# DaughterBoard_Slots.net
KiCad netlist of a schematic drawn in Altium Designer
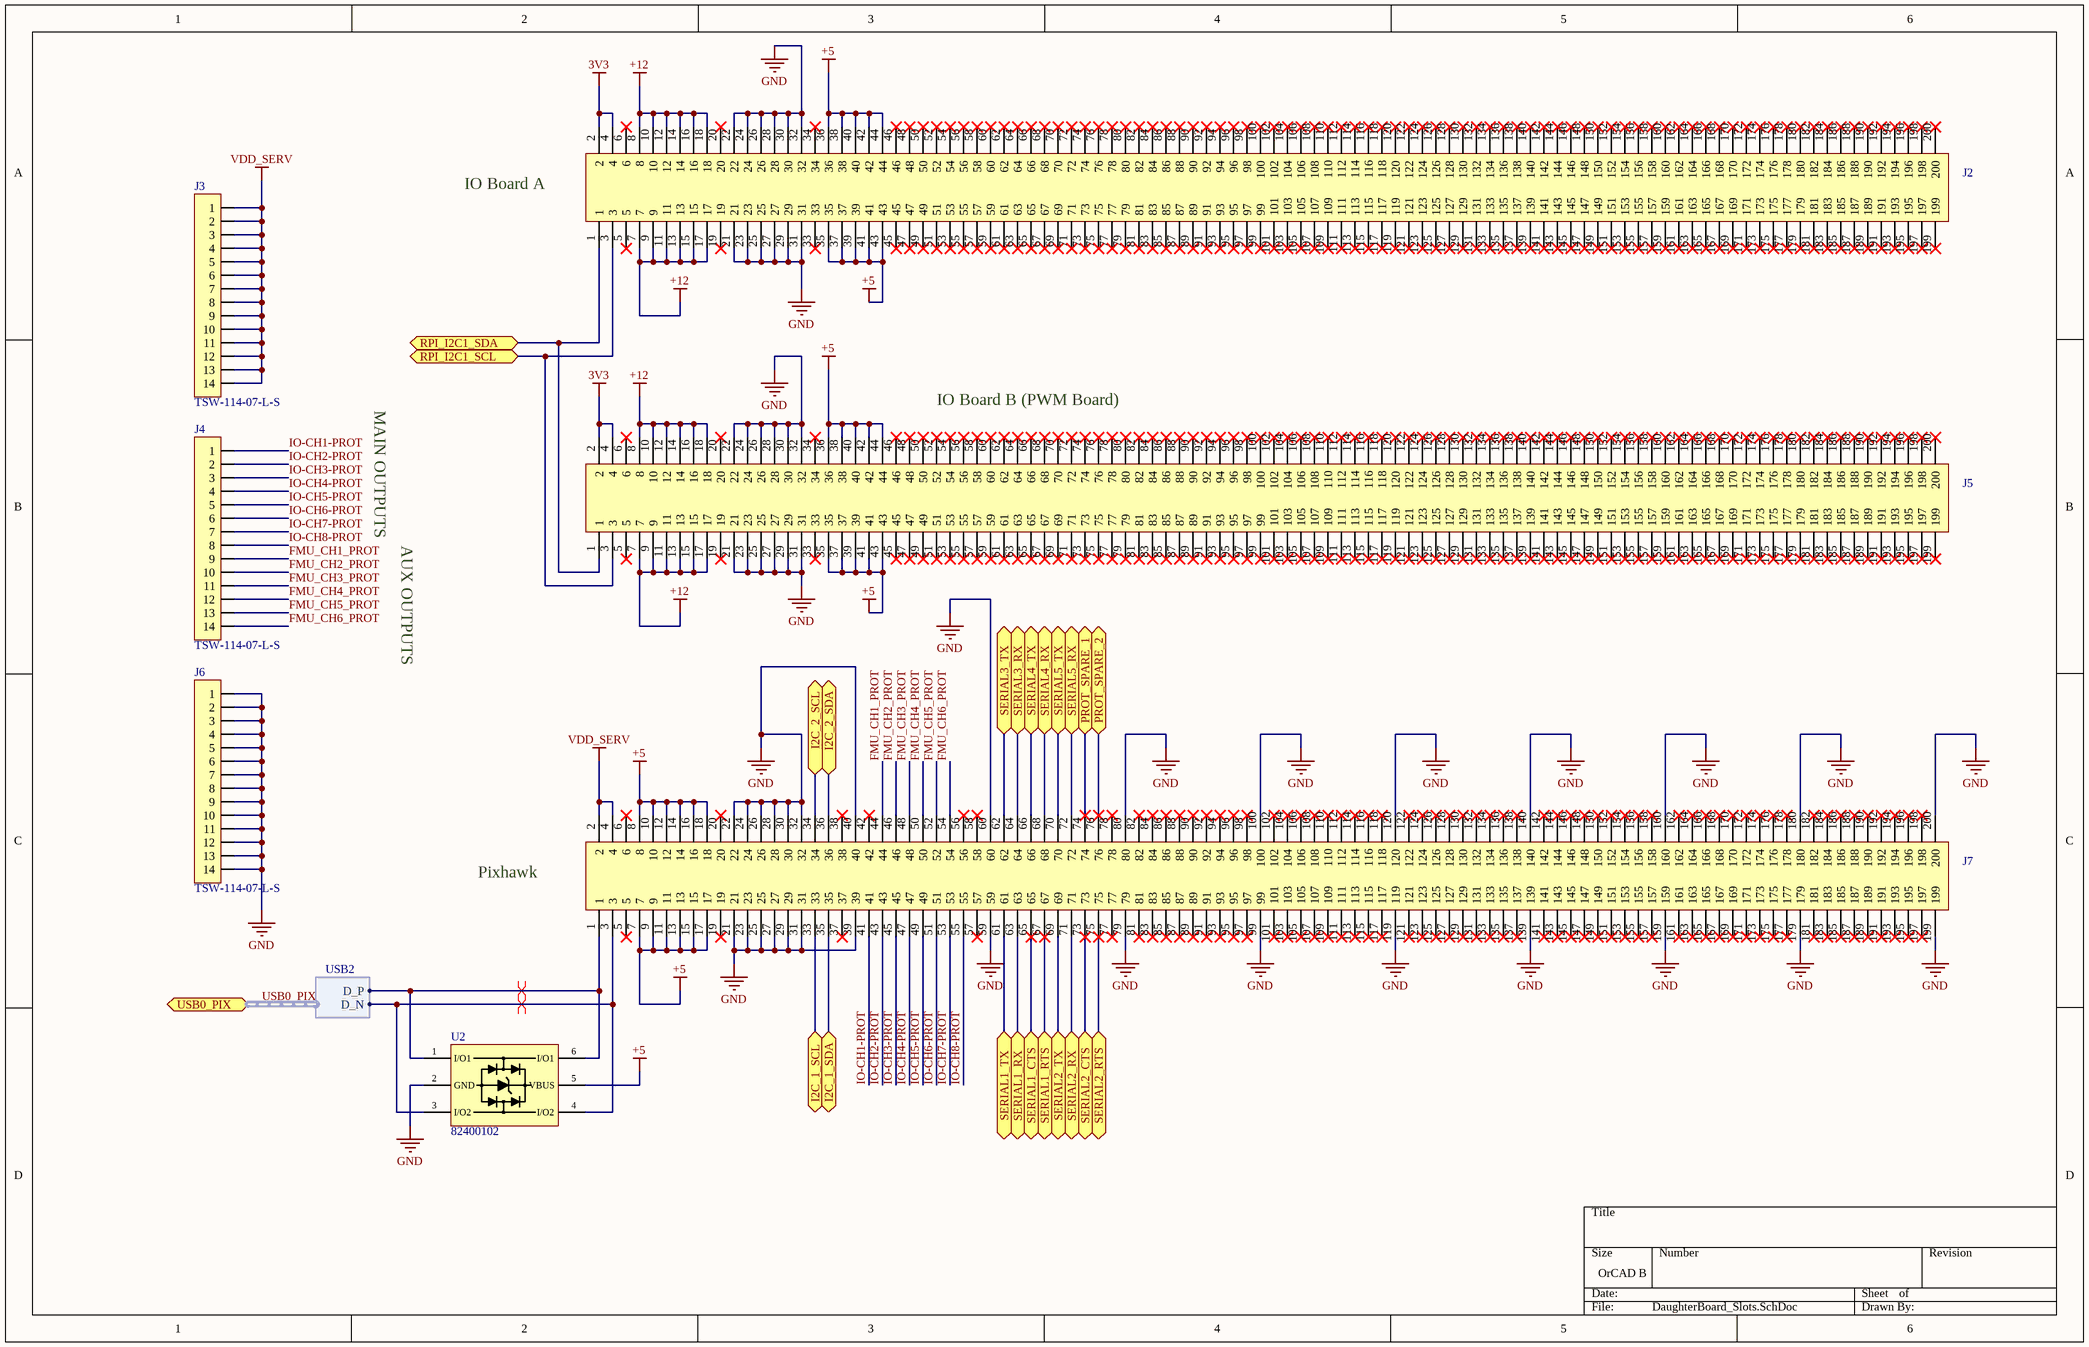
[diagram p0: DaughterBoard_Slots.SchDoc]

(export (version "E")
  (design (tool "Eeschema 10.0.6"))
  (components
    (comp (ref "J2")
      (value "conn-100x2_0")
      (footprint "DDR1-SODIMM-V")
      (description "Card-Edge Socket, DDR1 SODIMM (2.5V), 200-pin, Vertical")
      (fields (field (name "PART NUMBER") "CONN-00056") (field (name "MANUFACTURER") "TE Connectivity"))
      (libsource (lib "Connectors$") (part "CONN-00056"))
    )
    (comp (ref "J3")
      (value "TSW-114-07-L-S")
      (footprint "HDDR_14x1_0")
      (description "Header, 14x1, 0.1\"")
      (fields (field (name "PART NUMBER") "CONN-00117") (field (name "MANUFACTURER") "Samtec"))
      (libsource (lib "Connectors$") (part "CONN-00117"))
    )
    (comp (ref "J4")
      (value "TSW-114-07-L-S")
      (footprint "HDDR_14x1_0")
      (description "Header, 14x1, 0.1\"")
      (fields (field (name "PART NUMBER") "CONN-00117") (field (name "MANUFACTURER") "Samtec"))
      (libsource (lib "Connectors$") (part "CONN-00117"))
    )
    (comp (ref "J5")
      (value "conn-100x2_0")
      (footprint "DDR1-SODIMM-V")
      (description "Card-Edge Socket, DDR1 SODIMM (2.5V), 200-pin, Vertical")
      (fields (field (name "PART NUMBER") "CONN-00056") (field (name "MANUFACTURER") "TE Connectivity"))
      (libsource (lib "Connectors$") (part "CONN-00056"))
    )
    (comp (ref "J6")
      (value "TSW-114-07-L-S")
      (footprint "HDDR_14x1_0")
      (description "Header, 14x1, 0.1\"")
      (fields (field (name "PART NUMBER") "CONN-00117") (field (name "MANUFACTURER") "Samtec"))
      (libsource (lib "Connectors$") (part "CONN-00117"))
    )
    (comp (ref "J7")
      (value "conn-100x2_0")
      (footprint "DDR1-SODIMM-V")
      (description "Card-Edge Socket, DDR1 SODIMM (2.5V), 200-pin, Vertical")
      (fields (field (name "PART NUMBER") "CONN-00056") (field (name "MANUFACTURER") "TE Connectivity"))
      (libsource (lib "Connectors$") (part "CONN-00056"))
    )
    (comp (ref "U2")
      (value "82400102")
      (footprint "sot-23-6")
      (description "ESD Protec, 2-Ch, 2.5pF, 17V clamping voltage, SOT23-6")
      (fields (field (name "PART NUMBER") "DIO-00069") (field (name "MANUFACTURER") "ST"))
      (libsource (lib "Diodes$") (part "DIO-00069"))
    )
  )
  (nets
    (net (code "2") (name "+5") (class "Default")
      (node (ref "J2") (pin "35") (pinfunction "35_35") (pintype "passive"))
      (node (ref "J2") (pin "36") (pinfunction "36_36") (pintype "passive"))
      (node (ref "J2") (pin "37") (pinfunction "37_37") (pintype "passive"))
      (node (ref "J2") (pin "38") (pinfunction "38_38") (pintype "passive"))
      (node (ref "J2") (pin "39") (pinfunction "39_39") (pintype "passive"))
      (node (ref "J2") (pin "40") (pinfunction "40_40") (pintype "passive"))
      (node (ref "J2") (pin "41") (pinfunction "41_41") (pintype "passive"))
      (node (ref "J2") (pin "42") (pinfunction "42_42") (pintype "passive"))
      (node (ref "J2") (pin "43") (pinfunction "43_43") (pintype "passive"))
      (node (ref "J2") (pin "44") (pinfunction "44_44") (pintype "passive"))
      (node (ref "J5") (pin "35") (pinfunction "35_35") (pintype "passive"))
      (node (ref "J5") (pin "36") (pinfunction "36_36") (pintype "passive"))
      (node (ref "J5") (pin "37") (pinfunction "37_37") (pintype "passive"))
      (node (ref "J5") (pin "38") (pinfunction "38_38") (pintype "passive"))
      (node (ref "J5") (pin "39") (pinfunction "39_39") (pintype "passive"))
      (node (ref "J5") (pin "40") (pinfunction "40_40") (pintype "passive"))
      (node (ref "J5") (pin "41") (pinfunction "41_41") (pintype "passive"))
      (node (ref "J5") (pin "42") (pinfunction "42_42") (pintype "passive"))
      (node (ref "J5") (pin "43") (pinfunction "43_43") (pintype "passive"))
      (node (ref "J5") (pin "44") (pinfunction "44_44") (pintype "passive"))
      (node (ref "J7") (pin "10") (pinfunction "10_10") (pintype "passive"))
      (node (ref "J7") (pin "11") (pinfunction "11_11") (pintype "passive"))
      (node (ref "J7") (pin "12") (pinfunction "12_12") (pintype "passive"))
      (node (ref "J7") (pin "13") (pinfunction "13_13") (pintype "passive"))
      (node (ref "J7") (pin "14") (pinfunction "14_14") (pintype "passive"))
      (node (ref "J7") (pin "15") (pinfunction "15_15") (pintype "passive"))
      (node (ref "J7") (pin "16") (pinfunction "16_16") (pintype "passive"))
      (node (ref "J7") (pin "17") (pinfunction "17_17") (pintype "passive"))
      (node (ref "J7") (pin "18") (pinfunction "18_18") (pintype "passive"))
      (node (ref "J7") (pin "7") (pinfunction "7_7") (pintype "passive"))
      (node (ref "J7") (pin "8") (pinfunction "8_8") (pintype "passive"))
      (node (ref "J7") (pin "9") (pinfunction "9_9") (pintype "passive"))
      (node (ref "U2") (pin "5") (pinfunction "VBUS_5") (pintype "passive"))
    )
    (net (code "3") (name "+12") (class "Default")
      (node (ref "J2") (pin "10") (pinfunction "10_10") (pintype "passive"))
      (node (ref "J2") (pin "11") (pinfunction "11_11") (pintype "passive"))
      (node (ref "J2") (pin "12") (pinfunction "12_12") (pintype "passive"))
      (node (ref "J2") (pin "13") (pinfunction "13_13") (pintype "passive"))
      (node (ref "J2") (pin "14") (pinfunction "14_14") (pintype "passive"))
      (node (ref "J2") (pin "15") (pinfunction "15_15") (pintype "passive"))
      (node (ref "J2") (pin "16") (pinfunction "16_16") (pintype "passive"))
      (node (ref "J2") (pin "17") (pinfunction "17_17") (pintype "passive"))
      (node (ref "J2") (pin "18") (pinfunction "18_18") (pintype "passive"))
      (node (ref "J2") (pin "7") (pinfunction "7_7") (pintype "passive"))
      (node (ref "J2") (pin "8") (pinfunction "8_8") (pintype "passive"))
      (node (ref "J2") (pin "9") (pinfunction "9_9") (pintype "passive"))
      (node (ref "J5") (pin "10") (pinfunction "10_10") (pintype "passive"))
      (node (ref "J5") (pin "11") (pinfunction "11_11") (pintype "passive"))
      (node (ref "J5") (pin "12") (pinfunction "12_12") (pintype "passive"))
      (node (ref "J5") (pin "13") (pinfunction "13_13") (pintype "passive"))
      (node (ref "J5") (pin "14") (pinfunction "14_14") (pintype "passive"))
      (node (ref "J5") (pin "15") (pinfunction "15_15") (pintype "passive"))
      (node (ref "J5") (pin "16") (pinfunction "16_16") (pintype "passive"))
      (node (ref "J5") (pin "17") (pinfunction "17_17") (pintype "passive"))
      (node (ref "J5") (pin "18") (pinfunction "18_18") (pintype "passive"))
      (node (ref "J5") (pin "7") (pinfunction "7_7") (pintype "passive"))
      (node (ref "J5") (pin "8") (pinfunction "8_8") (pintype "passive"))
      (node (ref "J5") (pin "9") (pinfunction "9_9") (pintype "passive"))
    )
    (net (code "4") (name "/FMU_CH1_PROT") (class "Default")
      (node (ref "J4") (pin "9") (pinfunction "9_9") (pintype "passive"))
      (node (ref "J7") (pin "44") (pinfunction "44_44") (pintype "passive"))
    )
    (net (code "5") (name "/FMU_CH2_PROT") (class "Default")
      (node (ref "J4") (pin "10") (pinfunction "10_10") (pintype "passive"))
      (node (ref "J7") (pin "46") (pinfunction "46_46") (pintype "passive"))
    )
    (net (code "6") (name "/FMU_CH3_PROT") (class "Default")
      (node (ref "J4") (pin "11") (pinfunction "11_11") (pintype "passive"))
      (node (ref "J7") (pin "48") (pinfunction "48_48") (pintype "passive"))
    )
    (net (code "7") (name "/FMU_CH4_PROT") (class "Default")
      (node (ref "J4") (pin "12") (pinfunction "12_12") (pintype "passive"))
      (node (ref "J7") (pin "50") (pinfunction "50_50") (pintype "passive"))
    )
    (net (code "8") (name "/FMU_CH5_PROT") (class "Default")
      (node (ref "J4") (pin "13") (pinfunction "13_13") (pintype "passive"))
      (node (ref "J7") (pin "52") (pinfunction "52_52") (pintype "passive"))
    )
    (net (code "9") (name "/FMU_CH6_PROT") (class "Default")
      (node (ref "J4") (pin "14") (pinfunction "14_14") (pintype "passive"))
      (node (ref "J7") (pin "54") (pinfunction "54_54") (pintype "passive"))
    )
    (net (code "10") (name "/I2C_1_SCL") (class "Default")
      (node (ref "J7") (pin "33") (pinfunction "33_33") (pintype "passive"))
    )
    (net (code "11") (name "/I2C_1_SDA") (class "Default")
      (node (ref "J7") (pin "35") (pinfunction "35_35") (pintype "passive"))
    )
    (net (code "12") (name "/I2C_2_SCL") (class "Default")
      (node (ref "J7") (pin "34") (pinfunction "34_34") (pintype "passive"))
    )
    (net (code "13") (name "/I2C_2_SDA") (class "Default")
      (node (ref "J7") (pin "36") (pinfunction "36_36") (pintype "passive"))
    )
    (net (code "14") (name "/IO-CH1-PROT") (class "Default")
      (node (ref "J4") (pin "1") (pinfunction "1_1") (pintype "passive"))
      (node (ref "J7") (pin "41") (pinfunction "41_41") (pintype "passive"))
    )
    (net (code "15") (name "/IO-CH2-PROT") (class "Default")
      (node (ref "J4") (pin "2") (pinfunction "2_2") (pintype "passive"))
      (node (ref "J7") (pin "43") (pinfunction "43_43") (pintype "passive"))
    )
    (net (code "16") (name "/IO-CH3-PROT") (class "Default")
      (node (ref "J4") (pin "3") (pinfunction "3_3") (pintype "passive"))
      (node (ref "J7") (pin "45") (pinfunction "45_45") (pintype "passive"))
    )
    (net (code "17") (name "/IO-CH4-PROT") (class "Default")
      (node (ref "J4") (pin "4") (pinfunction "4_4") (pintype "passive"))
      (node (ref "J7") (pin "47") (pinfunction "47_47") (pintype "passive"))
    )
    (net (code "18") (name "/IO-CH5-PROT") (class "Default")
      (node (ref "J4") (pin "5") (pinfunction "5_5") (pintype "passive"))
      (node (ref "J7") (pin "49") (pinfunction "49_49") (pintype "passive"))
    )
    (net (code "19") (name "/IO-CH6-PROT") (class "Default")
      (node (ref "J4") (pin "6") (pinfunction "6_6") (pintype "passive"))
      (node (ref "J7") (pin "51") (pinfunction "51_51") (pintype "passive"))
    )
    (net (code "20") (name "/IO-CH7-PROT") (class "Default")
      (node (ref "J4") (pin "7") (pinfunction "7_7") (pintype "passive"))
      (node (ref "J7") (pin "53") (pinfunction "53_53") (pintype "passive"))
    )
    (net (code "21") (name "/IO-CH8-PROT") (class "Default")
      (node (ref "J4") (pin "8") (pinfunction "8_8") (pintype "passive"))
      (node (ref "J7") (pin "55") (pinfunction "55_55") (pintype "passive"))
    )
    (net (code "22") (name "/PROT_SPARE_1") (class "Default")
      (node (ref "J7") (pin "74") (pinfunction "74_74") (pintype "passive+no_connect"))
    )
    (net (code "23") (name "/PROT_SPARE_2") (class "Default")
      (node (ref "J7") (pin "76") (pinfunction "76_76") (pintype "passive+no_connect"))
    )
    (net (code "24") (name "/RPI_I2C1_SCL") (class "Default")
      (node (ref "J2") (pin "3") (pinfunction "3_3") (pintype "passive"))
      (node (ref "J5") (pin "3") (pinfunction "3_3") (pintype "passive"))
    )
    (net (code "25") (name "/RPI_I2C1_SDA") (class "Default")
      (node (ref "J2") (pin "1") (pinfunction "1_1") (pintype "passive"))
      (node (ref "J5") (pin "1") (pinfunction "1_1") (pintype "passive"))
    )
    (net (code "26") (name "/SERIAL1_CTS") (class "Default")
      (node (ref "J7") (pin "65") (pinfunction "65_65") (pintype "passive+no_connect"))
    )
    (net (code "27") (name "/SERIAL1_RTS") (class "Default")
      (node (ref "J7") (pin "67") (pinfunction "67_67") (pintype "passive+no_connect"))
    )
    (net (code "28") (name "/SERIAL1_RX") (class "Default")
      (node (ref "J7") (pin "63") (pinfunction "63_63") (pintype "passive"))
    )
    (net (code "29") (name "/SERIAL1_TX") (class "Default")
      (node (ref "J7") (pin "61") (pinfunction "61_61") (pintype "passive"))
    )
    (net (code "30") (name "/SERIAL2_CTS") (class "Default")
      (node (ref "J7") (pin "73") (pinfunction "73_73") (pintype "passive+no_connect"))
    )
    (net (code "31") (name "/SERIAL2_RTS") (class "Default")
      (node (ref "J7") (pin "75") (pinfunction "75_75") (pintype "passive+no_connect"))
    )
    (net (code "32") (name "/SERIAL2_RX") (class "Default")
      (node (ref "J7") (pin "71") (pinfunction "71_71") (pintype "passive"))
    )
    (net (code "33") (name "/SERIAL2_TX") (class "Default")
      (node (ref "J7") (pin "69") (pinfunction "69_69") (pintype "passive"))
    )
    (net (code "34") (name "/SERIAL3_RX") (class "Default")
      (node (ref "J7") (pin "64") (pinfunction "64_64") (pintype "passive"))
    )
    (net (code "35") (name "/SERIAL3_TX") (class "Default")
      (node (ref "J7") (pin "62") (pinfunction "62_62") (pintype "passive"))
    )
    (net (code "36") (name "/SERIAL4_RX") (class "Default")
      (node (ref "J7") (pin "68") (pinfunction "68_68") (pintype "passive"))
    )
    (net (code "37") (name "/SERIAL4_TX") (class "Default")
      (node (ref "J7") (pin "66") (pinfunction "66_66") (pintype "passive"))
    )
    (net (code "38") (name "/SERIAL5_RX") (class "Default")
      (node (ref "J7") (pin "72") (pinfunction "72_72") (pintype "passive"))
    )
    (net (code "39") (name "/SERIAL5_TX") (class "Default")
      (node (ref "J7") (pin "70") (pinfunction "70_70") (pintype "passive"))
    )
    (net (code "41") (name "3V3") (class "Default")
      (node (ref "J2") (pin "2") (pinfunction "2_2") (pintype "passive"))
      (node (ref "J2") (pin "4") (pinfunction "4_4") (pintype "passive"))
      (node (ref "J5") (pin "2") (pinfunction "2_2") (pintype "passive"))
      (node (ref "J5") (pin "4") (pinfunction "4_4") (pintype "passive"))
    )
    (net (code "42") (name "GND") (class "Default")
      (node (ref "J2") (pin "21") (pinfunction "21_21") (pintype "passive"))
      (node (ref "J2") (pin "22") (pinfunction "22_22") (pintype "passive"))
      (node (ref "J2") (pin "23") (pinfunction "23_23") (pintype "passive"))
      (node (ref "J2") (pin "24") (pinfunction "24_24") (pintype "passive"))
      (node (ref "J2") (pin "25") (pinfunction "25_25") (pintype "passive"))
      (node (ref "J2") (pin "26") (pinfunction "26_26") (pintype "passive"))
      (node (ref "J2") (pin "27") (pinfunction "27_27") (pintype "passive"))
      (node (ref "J2") (pin "28") (pinfunction "28_28") (pintype "passive"))
      (node (ref "J2") (pin "29") (pinfunction "29_29") (pintype "passive"))
      (node (ref "J2") (pin "30") (pinfunction "30_30") (pintype "passive"))
      (node (ref "J2") (pin "31") (pinfunction "31_31") (pintype "passive"))
      (node (ref "J2") (pin "32") (pinfunction "32_32") (pintype "passive"))
      (node (ref "J5") (pin "21") (pinfunction "21_21") (pintype "passive"))
      (node (ref "J5") (pin "22") (pinfunction "22_22") (pintype "passive"))
      (node (ref "J5") (pin "23") (pinfunction "23_23") (pintype "passive"))
      (node (ref "J5") (pin "24") (pinfunction "24_24") (pintype "passive"))
      (node (ref "J5") (pin "25") (pinfunction "25_25") (pintype "passive"))
      (node (ref "J5") (pin "26") (pinfunction "26_26") (pintype "passive"))
      (node (ref "J5") (pin "27") (pinfunction "27_27") (pintype "passive"))
      (node (ref "J5") (pin "28") (pinfunction "28_28") (pintype "passive"))
      (node (ref "J5") (pin "29") (pinfunction "29_29") (pintype "passive"))
      (node (ref "J5") (pin "30") (pinfunction "30_30") (pintype "passive"))
      (node (ref "J5") (pin "31") (pinfunction "31_31") (pintype "passive"))
      (node (ref "J5") (pin "32") (pinfunction "32_32") (pintype "passive"))
      (node (ref "J6") (pin "1") (pinfunction "1_1") (pintype "passive"))
      (node (ref "J6") (pin "10") (pinfunction "10_10") (pintype "passive"))
      (node (ref "J6") (pin "11") (pinfunction "11_11") (pintype "passive"))
      (node (ref "J6") (pin "12") (pinfunction "12_12") (pintype "passive"))
      (node (ref "J6") (pin "13") (pinfunction "13_13") (pintype "passive"))
      (node (ref "J6") (pin "14") (pinfunction "14_14") (pintype "passive"))
      (node (ref "J6") (pin "2") (pinfunction "2_2") (pintype "passive"))
      (node (ref "J6") (pin "3") (pinfunction "3_3") (pintype "passive"))
      (node (ref "J6") (pin "4") (pinfunction "4_4") (pintype "passive"))
      (node (ref "J6") (pin "5") (pinfunction "5_5") (pintype "passive"))
      (node (ref "J6") (pin "6") (pinfunction "6_6") (pintype "passive"))
      (node (ref "J6") (pin "7") (pinfunction "7_7") (pintype "passive"))
      (node (ref "J6") (pin "8") (pinfunction "8_8") (pintype "passive"))
      (node (ref "J6") (pin "9") (pinfunction "9_9") (pintype "passive"))
      (node (ref "J7") (pin "100") (pinfunction "100_100") (pintype "passive"))
      (node (ref "J7") (pin "119") (pinfunction "119_119") (pintype "passive"))
      (node (ref "J7") (pin "120") (pinfunction "120_120") (pintype "passive"))
      (node (ref "J7") (pin "139") (pinfunction "139_139") (pintype "passive"))
      (node (ref "J7") (pin "140") (pinfunction "140_140") (pintype "passive"))
      (node (ref "J7") (pin "159") (pinfunction "159_159") (pintype "passive"))
      (node (ref "J7") (pin "160") (pinfunction "160_160") (pintype "passive"))
      (node (ref "J7") (pin "179") (pinfunction "179_179") (pintype "passive"))
      (node (ref "J7") (pin "180") (pinfunction "180_180") (pintype "passive"))
      (node (ref "J7") (pin "199") (pinfunction "199_199") (pintype "passive"))
      (node (ref "J7") (pin "200") (pinfunction "200_200") (pintype "passive"))
      (node (ref "J7") (pin "21") (pinfunction "21_21") (pintype "passive"))
      (node (ref "J7") (pin "22") (pinfunction "22_22") (pintype "passive"))
      (node (ref "J7") (pin "23") (pinfunction "23_23") (pintype "passive"))
      (node (ref "J7") (pin "24") (pinfunction "24_24") (pintype "passive"))
      (node (ref "J7") (pin "25") (pinfunction "25_25") (pintype "passive"))
      (node (ref "J7") (pin "26") (pinfunction "26_26") (pintype "passive"))
      (node (ref "J7") (pin "27") (pinfunction "27_27") (pintype "passive"))
      (node (ref "J7") (pin "28") (pinfunction "28_28") (pintype "passive"))
      (node (ref "J7") (pin "29") (pinfunction "29_29") (pintype "passive"))
      (node (ref "J7") (pin "30") (pinfunction "30_30") (pintype "passive"))
      (node (ref "J7") (pin "31") (pinfunction "31_31") (pintype "passive"))
      (node (ref "J7") (pin "32") (pinfunction "32_32") (pintype "passive"))
      (node (ref "J7") (pin "39") (pinfunction "39_39") (pintype "passive"))
      (node (ref "J7") (pin "40") (pinfunction "40_40") (pintype "passive"))
      (node (ref "J7") (pin "59") (pinfunction "59_59") (pintype "passive"))
      (node (ref "J7") (pin "60") (pinfunction "60_60") (pintype "passive"))
      (node (ref "J7") (pin "79") (pinfunction "79_79") (pintype "passive"))
      (node (ref "J7") (pin "80") (pinfunction "80_80") (pintype "passive"))
      (node (ref "J7") (pin "99") (pinfunction "99_99") (pintype "passive"))
      (node (ref "U2") (pin "2") (pinfunction "GND_2") (pintype "passive"))
    )
    (net (code "43") (name "Net-(J7-Pad1)") (class "Default")
      (node (ref "J7") (pin "1") (pinfunction "1_1") (pintype "passive"))
      (node (ref "U2") (pin "1") (pinfunction "I/O1_1") (pintype "passive"))
      (node (ref "U2") (pin "6") (pinfunction "I/O1_6") (pintype "passive"))
    )
    (net (code "44") (name "Net-(J7-Pad3)") (class "Default")
      (node (ref "J7") (pin "3") (pinfunction "3_3") (pintype "passive"))
      (node (ref "U2") (pin "3") (pinfunction "I/O2_3") (pintype "passive"))
      (node (ref "U2") (pin "4") (pinfunction "I/O2_4") (pintype "passive"))
    )
    (net (code "45") (name "VDD_SERV") (class "Default")
      (node (ref "J3") (pin "1") (pinfunction "1_1") (pintype "passive"))
      (node (ref "J3") (pin "10") (pinfunction "10_10") (pintype "passive"))
      (node (ref "J3") (pin "11") (pinfunction "11_11") (pintype "passive"))
      (node (ref "J3") (pin "12") (pinfunction "12_12") (pintype "passive"))
      (node (ref "J3") (pin "13") (pinfunction "13_13") (pintype "passive"))
      (node (ref "J3") (pin "14") (pinfunction "14_14") (pintype "passive"))
      (node (ref "J3") (pin "2") (pinfunction "2_2") (pintype "passive"))
      (node (ref "J3") (pin "3") (pinfunction "3_3") (pintype "passive"))
      (node (ref "J3") (pin "4") (pinfunction "4_4") (pintype "passive"))
      (node (ref "J3") (pin "5") (pinfunction "5_5") (pintype "passive"))
      (node (ref "J3") (pin "6") (pinfunction "6_6") (pintype "passive"))
      (node (ref "J3") (pin "7") (pinfunction "7_7") (pintype "passive"))
      (node (ref "J3") (pin "8") (pinfunction "8_8") (pintype "passive"))
      (node (ref "J3") (pin "9") (pinfunction "9_9") (pintype "passive"))
      (node (ref "J7") (pin "2") (pinfunction "2_2") (pintype "passive"))
      (node (ref "J7") (pin "4") (pinfunction "4_4") (pintype "passive"))
    )
    (net (code "46") (name "unconnected-(J2-Pad5)") (class "Default")
      (node (ref "J2") (pin "5") (pinfunction "5_5") (pintype "passive+no_connect"))
    )
    (net (code "47") (name "unconnected-(J2-Pad6)") (class "Default")
      (node (ref "J2") (pin "6") (pinfunction "6_6") (pintype "passive+no_connect"))
    )
    (net (code "48") (name "unconnected-(J2-Pad19)") (class "Default")
      (node (ref "J2") (pin "19") (pinfunction "19_19") (pintype "passive+no_connect"))
    )
    (net (code "49") (name "unconnected-(J2-Pad20)") (class "Default")
      (node (ref "J2") (pin "20") (pinfunction "20_20") (pintype "passive+no_connect"))
    )
    (net (code "50") (name "unconnected-(J2-Pad33)") (class "Default")
      (node (ref "J2") (pin "33") (pinfunction "33_33") (pintype "passive+no_connect"))
    )
    (net (code "51") (name "unconnected-(J2-Pad34)") (class "Default")
      (node (ref "J2") (pin "34") (pinfunction "34_34") (pintype "passive+no_connect"))
    )
    (net (code "52") (name "unconnected-(J2-Pad45)") (class "Default")
      (node (ref "J2") (pin "45") (pinfunction "45_45") (pintype "passive+no_connect"))
    )
    (net (code "53") (name "unconnected-(J2-Pad46)") (class "Default")
      (node (ref "J2") (pin "46") (pinfunction "46_46") (pintype "passive+no_connect"))
    )
    (net (code "54") (name "unconnected-(J2-Pad47)") (class "Default")
      (node (ref "J2") (pin "47") (pinfunction "47_47") (pintype "passive+no_connect"))
    )
    (net (code "55") (name "unconnected-(J2-Pad48)") (class "Default")
      (node (ref "J2") (pin "48") (pinfunction "48_48") (pintype "passive+no_connect"))
    )
    (net (code "56") (name "unconnected-(J2-Pad49)") (class "Default")
      (node (ref "J2") (pin "49") (pinfunction "49_49") (pintype "passive+no_connect"))
    )
    (net (code "57") (name "unconnected-(J2-Pad50)") (class "Default")
      (node (ref "J2") (pin "50") (pinfunction "50_50") (pintype "passive+no_connect"))
    )
    (net (code "58") (name "unconnected-(J2-Pad51)") (class "Default")
      (node (ref "J2") (pin "51") (pinfunction "51_51") (pintype "passive+no_connect"))
    )
    (net (code "59") (name "unconnected-(J2-Pad52)") (class "Default")
      (node (ref "J2") (pin "52") (pinfunction "52_52") (pintype "passive+no_connect"))
    )
    (net (code "60") (name "unconnected-(J2-Pad53)") (class "Default")
      (node (ref "J2") (pin "53") (pinfunction "53_53") (pintype "passive+no_connect"))
    )
    (net (code "61") (name "unconnected-(J2-Pad54)") (class "Default")
      (node (ref "J2") (pin "54") (pinfunction "54_54") (pintype "passive+no_connect"))
    )
    (net (code "62") (name "unconnected-(J2-Pad55)") (class "Default")
      (node (ref "J2") (pin "55") (pinfunction "55_55") (pintype "passive+no_connect"))
    )
    (net (code "63") (name "unconnected-(J2-Pad56)") (class "Default")
      (node (ref "J2") (pin "56") (pinfunction "56_56") (pintype "passive+no_connect"))
    )
    (net (code "64") (name "unconnected-(J2-Pad57)") (class "Default")
      (node (ref "J2") (pin "57") (pinfunction "57_57") (pintype "passive+no_connect"))
    )
    (net (code "65") (name "unconnected-(J2-Pad58)") (class "Default")
      (node (ref "J2") (pin "58") (pinfunction "58_58") (pintype "passive+no_connect"))
    )
    (net (code "66") (name "unconnected-(J2-Pad59)") (class "Default")
      (node (ref "J2") (pin "59") (pinfunction "59_59") (pintype "passive+no_connect"))
    )
    (net (code "67") (name "unconnected-(J2-Pad60)") (class "Default")
      (node (ref "J2") (pin "60") (pinfunction "60_60") (pintype "passive+no_connect"))
    )
    (net (code "68") (name "unconnected-(J2-Pad61)") (class "Default")
      (node (ref "J2") (pin "61") (pinfunction "61_61") (pintype "passive+no_connect"))
    )
    (net (code "69") (name "unconnected-(J2-Pad62)") (class "Default")
      (node (ref "J2") (pin "62") (pinfunction "62_62") (pintype "passive+no_connect"))
    )
    (net (code "70") (name "unconnected-(J2-Pad63)") (class "Default")
      (node (ref "J2") (pin "63") (pinfunction "63_63") (pintype "passive+no_connect"))
    )
    (net (code "71") (name "unconnected-(J2-Pad64)") (class "Default")
      (node (ref "J2") (pin "64") (pinfunction "64_64") (pintype "passive+no_connect"))
    )
    (net (code "72") (name "unconnected-(J2-Pad65)") (class "Default")
      (node (ref "J2") (pin "65") (pinfunction "65_65") (pintype "passive+no_connect"))
    )
    (net (code "73") (name "unconnected-(J2-Pad66)") (class "Default")
      (node (ref "J2") (pin "66") (pinfunction "66_66") (pintype "passive+no_connect"))
    )
    (net (code "74") (name "unconnected-(J2-Pad67)") (class "Default")
      (node (ref "J2") (pin "67") (pinfunction "67_67") (pintype "passive+no_connect"))
    )
    (net (code "75") (name "unconnected-(J2-Pad68)") (class "Default")
      (node (ref "J2") (pin "68") (pinfunction "68_68") (pintype "passive+no_connect"))
    )
    (net (code "76") (name "unconnected-(J2-Pad69)") (class "Default")
      (node (ref "J2") (pin "69") (pinfunction "69_69") (pintype "passive+no_connect"))
    )
    (net (code "77") (name "unconnected-(J2-Pad70)") (class "Default")
      (node (ref "J2") (pin "70") (pinfunction "70_70") (pintype "passive+no_connect"))
    )
    (net (code "78") (name "unconnected-(J2-Pad71)") (class "Default")
      (node (ref "J2") (pin "71") (pinfunction "71_71") (pintype "passive+no_connect"))
    )
    (net (code "79") (name "unconnected-(J2-Pad72)") (class "Default")
      (node (ref "J2") (pin "72") (pinfunction "72_72") (pintype "passive+no_connect"))
    )
    (net (code "80") (name "unconnected-(J2-Pad73)") (class "Default")
      (node (ref "J2") (pin "73") (pinfunction "73_73") (pintype "passive+no_connect"))
    )
    (net (code "81") (name "unconnected-(J2-Pad74)") (class "Default")
      (node (ref "J2") (pin "74") (pinfunction "74_74") (pintype "passive+no_connect"))
    )
    (net (code "82") (name "unconnected-(J2-Pad75)") (class "Default")
      (node (ref "J2") (pin "75") (pinfunction "75_75") (pintype "passive+no_connect"))
    )
    (net (code "83") (name "unconnected-(J2-Pad76)") (class "Default")
      (node (ref "J2") (pin "76") (pinfunction "76_76") (pintype "passive+no_connect"))
    )
    (net (code "84") (name "unconnected-(J2-Pad77)") (class "Default")
      (node (ref "J2") (pin "77") (pinfunction "77_77") (pintype "passive+no_connect"))
    )
    (net (code "85") (name "unconnected-(J2-Pad78)") (class "Default")
      (node (ref "J2") (pin "78") (pinfunction "78_78") (pintype "passive+no_connect"))
    )
    (net (code "86") (name "unconnected-(J2-Pad79)") (class "Default")
      (node (ref "J2") (pin "79") (pinfunction "79_79") (pintype "passive+no_connect"))
    )
    (net (code "87") (name "unconnected-(J2-Pad80)") (class "Default")
      (node (ref "J2") (pin "80") (pinfunction "80_80") (pintype "passive+no_connect"))
    )
    (net (code "88") (name "unconnected-(J2-Pad81)") (class "Default")
      (node (ref "J2") (pin "81") (pinfunction "81_81") (pintype "passive+no_connect"))
    )
    (net (code "89") (name "unconnected-(J2-Pad82)") (class "Default")
      (node (ref "J2") (pin "82") (pinfunction "82_82") (pintype "passive+no_connect"))
    )
    (net (code "90") (name "unconnected-(J2-Pad83)") (class "Default")
      (node (ref "J2") (pin "83") (pinfunction "83_83") (pintype "passive+no_connect"))
    )
    (net (code "91") (name "unconnected-(J2-Pad84)") (class "Default")
      (node (ref "J2") (pin "84") (pinfunction "84_84") (pintype "passive+no_connect"))
    )
    (net (code "92") (name "unconnected-(J2-Pad85)") (class "Default")
      (node (ref "J2") (pin "85") (pinfunction "85_85") (pintype "passive+no_connect"))
    )
    (net (code "93") (name "unconnected-(J2-Pad86)") (class "Default")
      (node (ref "J2") (pin "86") (pinfunction "86_86") (pintype "passive+no_connect"))
    )
    (net (code "94") (name "unconnected-(J2-Pad87)") (class "Default")
      (node (ref "J2") (pin "87") (pinfunction "87_87") (pintype "passive+no_connect"))
    )
    (net (code "95") (name "unconnected-(J2-Pad88)") (class "Default")
      (node (ref "J2") (pin "88") (pinfunction "88_88") (pintype "passive+no_connect"))
    )
    (net (code "96") (name "unconnected-(J2-Pad89)") (class "Default")
      (node (ref "J2") (pin "89") (pinfunction "89_89") (pintype "passive+no_connect"))
    )
    (net (code "97") (name "unconnected-(J2-Pad90)") (class "Default")
      (node (ref "J2") (pin "90") (pinfunction "90_90") (pintype "passive+no_connect"))
    )
    (net (code "98") (name "unconnected-(J2-Pad91)") (class "Default")
      (node (ref "J2") (pin "91") (pinfunction "91_91") (pintype "passive+no_connect"))
    )
    (net (code "99") (name "unconnected-(J2-Pad92)") (class "Default")
      (node (ref "J2") (pin "92") (pinfunction "92_92") (pintype "passive+no_connect"))
    )
    (net (code "100") (name "unconnected-(J2-Pad93)") (class "Default")
      (node (ref "J2") (pin "93") (pinfunction "93_93") (pintype "passive+no_connect"))
    )
    (net (code "101") (name "unconnected-(J2-Pad94)") (class "Default")
      (node (ref "J2") (pin "94") (pinfunction "94_94") (pintype "passive+no_connect"))
    )
    (net (code "102") (name "unconnected-(J2-Pad95)") (class "Default")
      (node (ref "J2") (pin "95") (pinfunction "95_95") (pintype "passive+no_connect"))
    )
    (net (code "103") (name "unconnected-(J2-Pad96)") (class "Default")
      (node (ref "J2") (pin "96") (pinfunction "96_96") (pintype "passive+no_connect"))
    )
    (net (code "104") (name "unconnected-(J2-Pad97)") (class "Default")
      (node (ref "J2") (pin "97") (pinfunction "97_97") (pintype "passive+no_connect"))
    )
    (net (code "105") (name "unconnected-(J2-Pad98)") (class "Default")
      (node (ref "J2") (pin "98") (pinfunction "98_98") (pintype "passive+no_connect"))
    )
    (net (code "106") (name "unconnected-(J2-Pad99)") (class "Default")
      (node (ref "J2") (pin "99") (pinfunction "99_99") (pintype "passive+no_connect"))
    )
    (net (code "107") (name "unconnected-(J2-Pad100)") (class "Default")
      (node (ref "J2") (pin "100") (pinfunction "100_100") (pintype "passive+no_connect"))
    )
    (net (code "108") (name "unconnected-(J2-Pad101)") (class "Default")
      (node (ref "J2") (pin "101") (pinfunction "101_101") (pintype "passive+no_connect"))
    )
    (net (code "109") (name "unconnected-(J2-Pad102)") (class "Default")
      (node (ref "J2") (pin "102") (pinfunction "102_102") (pintype "passive+no_connect"))
    )
    (net (code "110") (name "unconnected-(J2-Pad103)") (class "Default")
      (node (ref "J2") (pin "103") (pinfunction "103_103") (pintype "passive+no_connect"))
    )
    (net (code "111") (name "unconnected-(J2-Pad104)") (class "Default")
      (node (ref "J2") (pin "104") (pinfunction "104_104") (pintype "passive+no_connect"))
    )
    (net (code "112") (name "unconnected-(J2-Pad105)") (class "Default")
      (node (ref "J2") (pin "105") (pinfunction "105_105") (pintype "passive+no_connect"))
    )
    (net (code "113") (name "unconnected-(J2-Pad106)") (class "Default")
      (node (ref "J2") (pin "106") (pinfunction "106_106") (pintype "passive+no_connect"))
    )
    (net (code "114") (name "unconnected-(J2-Pad107)") (class "Default")
      (node (ref "J2") (pin "107") (pinfunction "107_107") (pintype "passive+no_connect"))
    )
    (net (code "115") (name "unconnected-(J2-Pad108)") (class "Default")
      (node (ref "J2") (pin "108") (pinfunction "108_108") (pintype "passive+no_connect"))
    )
    (net (code "116") (name "unconnected-(J2-Pad109)") (class "Default")
      (node (ref "J2") (pin "109") (pinfunction "109_109") (pintype "passive+no_connect"))
    )
    (net (code "117") (name "unconnected-(J2-Pad110)") (class "Default")
      (node (ref "J2") (pin "110") (pinfunction "110_110") (pintype "passive+no_connect"))
    )
    (net (code "118") (name "unconnected-(J2-Pad111)") (class "Default")
      (node (ref "J2") (pin "111") (pinfunction "111_111") (pintype "passive+no_connect"))
    )
    (net (code "119") (name "unconnected-(J2-Pad112)") (class "Default")
      (node (ref "J2") (pin "112") (pinfunction "112_112") (pintype "passive+no_connect"))
    )
    (net (code "120") (name "unconnected-(J2-Pad113)") (class "Default")
      (node (ref "J2") (pin "113") (pinfunction "113_113") (pintype "passive+no_connect"))
    )
    (net (code "121") (name "unconnected-(J2-Pad114)") (class "Default")
      (node (ref "J2") (pin "114") (pinfunction "114_114") (pintype "passive+no_connect"))
    )
    (net (code "122") (name "unconnected-(J2-Pad115)") (class "Default")
      (node (ref "J2") (pin "115") (pinfunction "115_115") (pintype "passive+no_connect"))
    )
    (net (code "123") (name "unconnected-(J2-Pad116)") (class "Default")
      (node (ref "J2") (pin "116") (pinfunction "116_116") (pintype "passive+no_connect"))
    )
    (net (code "124") (name "unconnected-(J2-Pad117)") (class "Default")
      (node (ref "J2") (pin "117") (pinfunction "117_117") (pintype "passive+no_connect"))
    )
    (net (code "125") (name "unconnected-(J2-Pad118)") (class "Default")
      (node (ref "J2") (pin "118") (pinfunction "118_118") (pintype "passive+no_connect"))
    )
    (net (code "126") (name "unconnected-(J2-Pad119)") (class "Default")
      (node (ref "J2") (pin "119") (pinfunction "119_119") (pintype "passive+no_connect"))
    )
    (net (code "127") (name "unconnected-(J2-Pad120)") (class "Default")
      (node (ref "J2") (pin "120") (pinfunction "120_120") (pintype "passive+no_connect"))
    )
    (net (code "128") (name "unconnected-(J2-Pad121)") (class "Default")
      (node (ref "J2") (pin "121") (pinfunction "121_121") (pintype "passive+no_connect"))
    )
    (net (code "129") (name "unconnected-(J2-Pad122)") (class "Default")
      (node (ref "J2") (pin "122") (pinfunction "122_122") (pintype "passive+no_connect"))
    )
    (net (code "130") (name "unconnected-(J2-Pad123)") (class "Default")
      (node (ref "J2") (pin "123") (pinfunction "123_123") (pintype "passive+no_connect"))
    )
    (net (code "131") (name "unconnected-(J2-Pad124)") (class "Default")
      (node (ref "J2") (pin "124") (pinfunction "124_124") (pintype "passive+no_connect"))
    )
    (net (code "132") (name "unconnected-(J2-Pad125)") (class "Default")
      (node (ref "J2") (pin "125") (pinfunction "125_125") (pintype "passive+no_connect"))
    )
    (net (code "133") (name "unconnected-(J2-Pad126)") (class "Default")
      (node (ref "J2") (pin "126") (pinfunction "126_126") (pintype "passive+no_connect"))
    )
    (net (code "134") (name "unconnected-(J2-Pad127)") (class "Default")
      (node (ref "J2") (pin "127") (pinfunction "127_127") (pintype "passive+no_connect"))
    )
    (net (code "135") (name "unconnected-(J2-Pad128)") (class "Default")
      (node (ref "J2") (pin "128") (pinfunction "128_128") (pintype "passive+no_connect"))
    )
    (net (code "136") (name "unconnected-(J2-Pad129)") (class "Default")
      (node (ref "J2") (pin "129") (pinfunction "129_129") (pintype "passive+no_connect"))
    )
    (net (code "137") (name "unconnected-(J2-Pad130)") (class "Default")
      (node (ref "J2") (pin "130") (pinfunction "130_130") (pintype "passive+no_connect"))
    )
    (net (code "138") (name "unconnected-(J2-Pad131)") (class "Default")
      (node (ref "J2") (pin "131") (pinfunction "131_131") (pintype "passive+no_connect"))
    )
    (net (code "139") (name "unconnected-(J2-Pad132)") (class "Default")
      (node (ref "J2") (pin "132") (pinfunction "132_132") (pintype "passive+no_connect"))
    )
    (net (code "140") (name "unconnected-(J2-Pad133)") (class "Default")
      (node (ref "J2") (pin "133") (pinfunction "133_133") (pintype "passive+no_connect"))
    )
    (net (code "141") (name "unconnected-(J2-Pad134)") (class "Default")
      (node (ref "J2") (pin "134") (pinfunction "134_134") (pintype "passive+no_connect"))
    )
    (net (code "142") (name "unconnected-(J2-Pad135)") (class "Default")
      (node (ref "J2") (pin "135") (pinfunction "135_135") (pintype "passive+no_connect"))
    )
    (net (code "143") (name "unconnected-(J2-Pad136)") (class "Default")
      (node (ref "J2") (pin "136") (pinfunction "136_136") (pintype "passive+no_connect"))
    )
    (net (code "144") (name "unconnected-(J2-Pad137)") (class "Default")
      (node (ref "J2") (pin "137") (pinfunction "137_137") (pintype "passive+no_connect"))
    )
    (net (code "145") (name "unconnected-(J2-Pad138)") (class "Default")
      (node (ref "J2") (pin "138") (pinfunction "138_138") (pintype "passive+no_connect"))
    )
    (net (code "146") (name "unconnected-(J2-Pad139)") (class "Default")
      (node (ref "J2") (pin "139") (pinfunction "139_139") (pintype "passive+no_connect"))
    )
    (net (code "147") (name "unconnected-(J2-Pad140)") (class "Default")
      (node (ref "J2") (pin "140") (pinfunction "140_140") (pintype "passive+no_connect"))
    )
    (net (code "148") (name "unconnected-(J2-Pad141)") (class "Default")
      (node (ref "J2") (pin "141") (pinfunction "141_141") (pintype "passive+no_connect"))
    )
    (net (code "149") (name "unconnected-(J2-Pad142)") (class "Default")
      (node (ref "J2") (pin "142") (pinfunction "142_142") (pintype "passive+no_connect"))
    )
    (net (code "150") (name "unconnected-(J2-Pad143)") (class "Default")
      (node (ref "J2") (pin "143") (pinfunction "143_143") (pintype "passive+no_connect"))
    )
    (net (code "151") (name "unconnected-(J2-Pad144)") (class "Default")
      (node (ref "J2") (pin "144") (pinfunction "144_144") (pintype "passive+no_connect"))
    )
    (net (code "152") (name "unconnected-(J2-Pad145)") (class "Default")
      (node (ref "J2") (pin "145") (pinfunction "145_145") (pintype "passive+no_connect"))
    )
    (net (code "153") (name "unconnected-(J2-Pad146)") (class "Default")
      (node (ref "J2") (pin "146") (pinfunction "146_146") (pintype "passive+no_connect"))
    )
    (net (code "154") (name "unconnected-(J2-Pad147)") (class "Default")
      (node (ref "J2") (pin "147") (pinfunction "147_147") (pintype "passive+no_connect"))
    )
    (net (code "155") (name "unconnected-(J2-Pad148)") (class "Default")
      (node (ref "J2") (pin "148") (pinfunction "148_148") (pintype "passive+no_connect"))
    )
    (net (code "156") (name "unconnected-(J2-Pad149)") (class "Default")
      (node (ref "J2") (pin "149") (pinfunction "149_149") (pintype "passive+no_connect"))
    )
    (net (code "157") (name "unconnected-(J2-Pad150)") (class "Default")
      (node (ref "J2") (pin "150") (pinfunction "150_150") (pintype "passive+no_connect"))
    )
    (net (code "158") (name "unconnected-(J2-Pad151)") (class "Default")
      (node (ref "J2") (pin "151") (pinfunction "151_151") (pintype "passive+no_connect"))
    )
    (net (code "159") (name "unconnected-(J2-Pad152)") (class "Default")
      (node (ref "J2") (pin "152") (pinfunction "152_152") (pintype "passive+no_connect"))
    )
    (net (code "160") (name "unconnected-(J2-Pad153)") (class "Default")
      (node (ref "J2") (pin "153") (pinfunction "153_153") (pintype "passive+no_connect"))
    )
    (net (code "161") (name "unconnected-(J2-Pad154)") (class "Default")
      (node (ref "J2") (pin "154") (pinfunction "154_154") (pintype "passive+no_connect"))
    )
    (net (code "162") (name "unconnected-(J2-Pad155)") (class "Default")
      (node (ref "J2") (pin "155") (pinfunction "155_155") (pintype "passive+no_connect"))
    )
    (net (code "163") (name "unconnected-(J2-Pad156)") (class "Default")
      (node (ref "J2") (pin "156") (pinfunction "156_156") (pintype "passive+no_connect"))
    )
    (net (code "164") (name "unconnected-(J2-Pad157)") (class "Default")
      (node (ref "J2") (pin "157") (pinfunction "157_157") (pintype "passive+no_connect"))
    )
    (net (code "165") (name "unconnected-(J2-Pad158)") (class "Default")
      (node (ref "J2") (pin "158") (pinfunction "158_158") (pintype "passive+no_connect"))
    )
    (net (code "166") (name "unconnected-(J2-Pad159)") (class "Default")
      (node (ref "J2") (pin "159") (pinfunction "159_159") (pintype "passive+no_connect"))
    )
    (net (code "167") (name "unconnected-(J2-Pad160)") (class "Default")
      (node (ref "J2") (pin "160") (pinfunction "160_160") (pintype "passive+no_connect"))
    )
    (net (code "168") (name "unconnected-(J2-Pad161)") (class "Default")
      (node (ref "J2") (pin "161") (pinfunction "161_161") (pintype "passive+no_connect"))
    )
    (net (code "169") (name "unconnected-(J2-Pad162)") (class "Default")
      (node (ref "J2") (pin "162") (pinfunction "162_162") (pintype "passive+no_connect"))
    )
    (net (code "170") (name "unconnected-(J2-Pad163)") (class "Default")
      (node (ref "J2") (pin "163") (pinfunction "163_163") (pintype "passive+no_connect"))
    )
    (net (code "171") (name "unconnected-(J2-Pad164)") (class "Default")
      (node (ref "J2") (pin "164") (pinfunction "164_164") (pintype "passive+no_connect"))
    )
    (net (code "172") (name "unconnected-(J2-Pad165)") (class "Default")
      (node (ref "J2") (pin "165") (pinfunction "165_165") (pintype "passive+no_connect"))
    )
    (net (code "173") (name "unconnected-(J2-Pad166)") (class "Default")
      (node (ref "J2") (pin "166") (pinfunction "166_166") (pintype "passive+no_connect"))
    )
    (net (code "174") (name "unconnected-(J2-Pad167)") (class "Default")
      (node (ref "J2") (pin "167") (pinfunction "167_167") (pintype "passive+no_connect"))
    )
    (net (code "175") (name "unconnected-(J2-Pad168)") (class "Default")
      (node (ref "J2") (pin "168") (pinfunction "168_168") (pintype "passive+no_connect"))
    )
    (net (code "176") (name "unconnected-(J2-Pad169)") (class "Default")
      (node (ref "J2") (pin "169") (pinfunction "169_169") (pintype "passive+no_connect"))
    )
    (net (code "177") (name "unconnected-(J2-Pad170)") (class "Default")
      (node (ref "J2") (pin "170") (pinfunction "170_170") (pintype "passive+no_connect"))
    )
    (net (code "178") (name "unconnected-(J2-Pad171)") (class "Default")
      (node (ref "J2") (pin "171") (pinfunction "171_171") (pintype "passive+no_connect"))
    )
    (net (code "179") (name "unconnected-(J2-Pad172)") (class "Default")
      (node (ref "J2") (pin "172") (pinfunction "172_172") (pintype "passive+no_connect"))
    )
    (net (code "180") (name "unconnected-(J2-Pad173)") (class "Default")
      (node (ref "J2") (pin "173") (pinfunction "173_173") (pintype "passive+no_connect"))
    )
    (net (code "181") (name "unconnected-(J2-Pad174)") (class "Default")
      (node (ref "J2") (pin "174") (pinfunction "174_174") (pintype "passive+no_connect"))
    )
    (net (code "182") (name "unconnected-(J2-Pad175)") (class "Default")
      (node (ref "J2") (pin "175") (pinfunction "175_175") (pintype "passive+no_connect"))
    )
    (net (code "183") (name "unconnected-(J2-Pad176)") (class "Default")
      (node (ref "J2") (pin "176") (pinfunction "176_176") (pintype "passive+no_connect"))
    )
    (net (code "184") (name "unconnected-(J2-Pad177)") (class "Default")
      (node (ref "J2") (pin "177") (pinfunction "177_177") (pintype "passive+no_connect"))
    )
    (net (code "185") (name "unconnected-(J2-Pad178)") (class "Default")
      (node (ref "J2") (pin "178") (pinfunction "178_178") (pintype "passive+no_connect"))
    )
    (net (code "186") (name "unconnected-(J2-Pad179)") (class "Default")
      (node (ref "J2") (pin "179") (pinfunction "179_179") (pintype "passive+no_connect"))
    )
    (net (code "187") (name "unconnected-(J2-Pad180)") (class "Default")
      (node (ref "J2") (pin "180") (pinfunction "180_180") (pintype "passive+no_connect"))
    )
    (net (code "188") (name "unconnected-(J2-Pad181)") (class "Default")
      (node (ref "J2") (pin "181") (pinfunction "181_181") (pintype "passive+no_connect"))
    )
    (net (code "189") (name "unconnected-(J2-Pad182)") (class "Default")
      (node (ref "J2") (pin "182") (pinfunction "182_182") (pintype "passive+no_connect"))
    )
    (net (code "190") (name "unconnected-(J2-Pad183)") (class "Default")
      (node (ref "J2") (pin "183") (pinfunction "183_183") (pintype "passive+no_connect"))
    )
    (net (code "191") (name "unconnected-(J2-Pad184)") (class "Default")
      (node (ref "J2") (pin "184") (pinfunction "184_184") (pintype "passive+no_connect"))
    )
    (net (code "192") (name "unconnected-(J2-Pad185)") (class "Default")
      (node (ref "J2") (pin "185") (pinfunction "185_185") (pintype "passive+no_connect"))
    )
    (net (code "193") (name "unconnected-(J2-Pad186)") (class "Default")
      (node (ref "J2") (pin "186") (pinfunction "186_186") (pintype "passive+no_connect"))
    )
    (net (code "194") (name "unconnected-(J2-Pad187)") (class "Default")
      (node (ref "J2") (pin "187") (pinfunction "187_187") (pintype "passive+no_connect"))
    )
    (net (code "195") (name "unconnected-(J2-Pad188)") (class "Default")
      (node (ref "J2") (pin "188") (pinfunction "188_188") (pintype "passive+no_connect"))
    )
    (net (code "196") (name "unconnected-(J2-Pad189)") (class "Default")
      (node (ref "J2") (pin "189") (pinfunction "189_189") (pintype "passive+no_connect"))
    )
    (net (code "197") (name "unconnected-(J2-Pad190)") (class "Default")
      (node (ref "J2") (pin "190") (pinfunction "190_190") (pintype "passive+no_connect"))
    )
    (net (code "198") (name "unconnected-(J2-Pad191)") (class "Default")
      (node (ref "J2") (pin "191") (pinfunction "191_191") (pintype "passive+no_connect"))
    )
    (net (code "199") (name "unconnected-(J2-Pad192)") (class "Default")
      (node (ref "J2") (pin "192") (pinfunction "192_192") (pintype "passive+no_connect"))
    )
    (net (code "200") (name "unconnected-(J2-Pad193)") (class "Default")
      (node (ref "J2") (pin "193") (pinfunction "193_193") (pintype "passive+no_connect"))
    )
    (net (code "201") (name "unconnected-(J2-Pad194)") (class "Default")
      (node (ref "J2") (pin "194") (pinfunction "194_194") (pintype "passive+no_connect"))
    )
    (net (code "202") (name "unconnected-(J2-Pad195)") (class "Default")
      (node (ref "J2") (pin "195") (pinfunction "195_195") (pintype "passive+no_connect"))
    )
    (net (code "203") (name "unconnected-(J2-Pad196)") (class "Default")
      (node (ref "J2") (pin "196") (pinfunction "196_196") (pintype "passive+no_connect"))
    )
    (net (code "204") (name "unconnected-(J2-Pad197)") (class "Default")
      (node (ref "J2") (pin "197") (pinfunction "197_197") (pintype "passive+no_connect"))
    )
    (net (code "205") (name "unconnected-(J2-Pad198)") (class "Default")
      (node (ref "J2") (pin "198") (pinfunction "198_198") (pintype "passive+no_connect"))
    )
    (net (code "206") (name "unconnected-(J2-Pad199)") (class "Default")
      (node (ref "J2") (pin "199") (pinfunction "199_199") (pintype "passive+no_connect"))
    )
    (net (code "207") (name "unconnected-(J2-Pad200)") (class "Default")
      (node (ref "J2") (pin "200") (pinfunction "200_200") (pintype "passive+no_connect"))
    )
    (net (code "208") (name "unconnected-(J5-Pad5)") (class "Default")
      (node (ref "J5") (pin "5") (pinfunction "5_5") (pintype "passive+no_connect"))
    )
    (net (code "209") (name "unconnected-(J5-Pad6)") (class "Default")
      (node (ref "J5") (pin "6") (pinfunction "6_6") (pintype "passive+no_connect"))
    )
    (net (code "210") (name "unconnected-(J5-Pad19)") (class "Default")
      (node (ref "J5") (pin "19") (pinfunction "19_19") (pintype "passive+no_connect"))
    )
    (net (code "211") (name "unconnected-(J5-Pad20)") (class "Default")
      (node (ref "J5") (pin "20") (pinfunction "20_20") (pintype "passive+no_connect"))
    )
    (net (code "212") (name "unconnected-(J5-Pad33)") (class "Default")
      (node (ref "J5") (pin "33") (pinfunction "33_33") (pintype "passive+no_connect"))
    )
    (net (code "213") (name "unconnected-(J5-Pad34)") (class "Default")
      (node (ref "J5") (pin "34") (pinfunction "34_34") (pintype "passive+no_connect"))
    )
    (net (code "214") (name "unconnected-(J5-Pad45)") (class "Default")
      (node (ref "J5") (pin "45") (pinfunction "45_45") (pintype "passive+no_connect"))
    )
    (net (code "215") (name "unconnected-(J5-Pad46)") (class "Default")
      (node (ref "J5") (pin "46") (pinfunction "46_46") (pintype "passive+no_connect"))
    )
    (net (code "216") (name "unconnected-(J5-Pad47)") (class "Default")
      (node (ref "J5") (pin "47") (pinfunction "47_47") (pintype "passive+no_connect"))
    )
    (net (code "217") (name "unconnected-(J5-Pad48)") (class "Default")
      (node (ref "J5") (pin "48") (pinfunction "48_48") (pintype "passive+no_connect"))
    )
    (net (code "218") (name "unconnected-(J5-Pad49)") (class "Default")
      (node (ref "J5") (pin "49") (pinfunction "49_49") (pintype "passive+no_connect"))
    )
    (net (code "219") (name "unconnected-(J5-Pad50)") (class "Default")
      (node (ref "J5") (pin "50") (pinfunction "50_50") (pintype "passive+no_connect"))
    )
    (net (code "220") (name "unconnected-(J5-Pad51)") (class "Default")
      (node (ref "J5") (pin "51") (pinfunction "51_51") (pintype "passive+no_connect"))
    )
    (net (code "221") (name "unconnected-(J5-Pad52)") (class "Default")
      (node (ref "J5") (pin "52") (pinfunction "52_52") (pintype "passive+no_connect"))
    )
    (net (code "222") (name "unconnected-(J5-Pad53)") (class "Default")
      (node (ref "J5") (pin "53") (pinfunction "53_53") (pintype "passive+no_connect"))
    )
    (net (code "223") (name "unconnected-(J5-Pad54)") (class "Default")
      (node (ref "J5") (pin "54") (pinfunction "54_54") (pintype "passive+no_connect"))
    )
    (net (code "224") (name "unconnected-(J5-Pad55)") (class "Default")
      (node (ref "J5") (pin "55") (pinfunction "55_55") (pintype "passive+no_connect"))
    )
    (net (code "225") (name "unconnected-(J5-Pad56)") (class "Default")
      (node (ref "J5") (pin "56") (pinfunction "56_56") (pintype "passive+no_connect"))
    )
    (net (code "226") (name "unconnected-(J5-Pad57)") (class "Default")
      (node (ref "J5") (pin "57") (pinfunction "57_57") (pintype "passive+no_connect"))
    )
    (net (code "227") (name "unconnected-(J5-Pad58)") (class "Default")
      (node (ref "J5") (pin "58") (pinfunction "58_58") (pintype "passive+no_connect"))
    )
    (net (code "228") (name "unconnected-(J5-Pad59)") (class "Default")
      (node (ref "J5") (pin "59") (pinfunction "59_59") (pintype "passive+no_connect"))
    )
    (net (code "229") (name "unconnected-(J5-Pad60)") (class "Default")
      (node (ref "J5") (pin "60") (pinfunction "60_60") (pintype "passive+no_connect"))
    )
    (net (code "230") (name "unconnected-(J5-Pad61)") (class "Default")
      (node (ref "J5") (pin "61") (pinfunction "61_61") (pintype "passive+no_connect"))
    )
    (net (code "231") (name "unconnected-(J5-Pad62)") (class "Default")
      (node (ref "J5") (pin "62") (pinfunction "62_62") (pintype "passive+no_connect"))
    )
    (net (code "232") (name "unconnected-(J5-Pad63)") (class "Default")
      (node (ref "J5") (pin "63") (pinfunction "63_63") (pintype "passive+no_connect"))
    )
    (net (code "233") (name "unconnected-(J5-Pad64)") (class "Default")
      (node (ref "J5") (pin "64") (pinfunction "64_64") (pintype "passive+no_connect"))
    )
    (net (code "234") (name "unconnected-(J5-Pad65)") (class "Default")
      (node (ref "J5") (pin "65") (pinfunction "65_65") (pintype "passive+no_connect"))
    )
    (net (code "235") (name "unconnected-(J5-Pad66)") (class "Default")
      (node (ref "J5") (pin "66") (pinfunction "66_66") (pintype "passive+no_connect"))
    )
    (net (code "236") (name "unconnected-(J5-Pad67)") (class "Default")
      (node (ref "J5") (pin "67") (pinfunction "67_67") (pintype "passive+no_connect"))
    )
    (net (code "237") (name "unconnected-(J5-Pad68)") (class "Default")
      (node (ref "J5") (pin "68") (pinfunction "68_68") (pintype "passive+no_connect"))
    )
    (net (code "238") (name "unconnected-(J5-Pad69)") (class "Default")
      (node (ref "J5") (pin "69") (pinfunction "69_69") (pintype "passive+no_connect"))
    )
    (net (code "239") (name "unconnected-(J5-Pad70)") (class "Default")
      (node (ref "J5") (pin "70") (pinfunction "70_70") (pintype "passive+no_connect"))
    )
    (net (code "240") (name "unconnected-(J5-Pad71)") (class "Default")
      (node (ref "J5") (pin "71") (pinfunction "71_71") (pintype "passive+no_connect"))
    )
    (net (code "241") (name "unconnected-(J5-Pad72)") (class "Default")
      (node (ref "J5") (pin "72") (pinfunction "72_72") (pintype "passive+no_connect"))
    )
    (net (code "242") (name "unconnected-(J5-Pad73)") (class "Default")
      (node (ref "J5") (pin "73") (pinfunction "73_73") (pintype "passive+no_connect"))
    )
    (net (code "243") (name "unconnected-(J5-Pad74)") (class "Default")
      (node (ref "J5") (pin "74") (pinfunction "74_74") (pintype "passive+no_connect"))
    )
    (net (code "244") (name "unconnected-(J5-Pad75)") (class "Default")
      (node (ref "J5") (pin "75") (pinfunction "75_75") (pintype "passive+no_connect"))
    )
    (net (code "245") (name "unconnected-(J5-Pad76)") (class "Default")
      (node (ref "J5") (pin "76") (pinfunction "76_76") (pintype "passive+no_connect"))
    )
    (net (code "246") (name "unconnected-(J5-Pad77)") (class "Default")
      (node (ref "J5") (pin "77") (pinfunction "77_77") (pintype "passive+no_connect"))
    )
    (net (code "247") (name "unconnected-(J5-Pad78)") (class "Default")
      (node (ref "J5") (pin "78") (pinfunction "78_78") (pintype "passive+no_connect"))
    )
    (net (code "248") (name "unconnected-(J5-Pad79)") (class "Default")
      (node (ref "J5") (pin "79") (pinfunction "79_79") (pintype "passive+no_connect"))
    )
    (net (code "249") (name "unconnected-(J5-Pad80)") (class "Default")
      (node (ref "J5") (pin "80") (pinfunction "80_80") (pintype "passive+no_connect"))
    )
    (net (code "250") (name "unconnected-(J5-Pad81)") (class "Default")
      (node (ref "J5") (pin "81") (pinfunction "81_81") (pintype "passive+no_connect"))
    )
    (net (code "251") (name "unconnected-(J5-Pad82)") (class "Default")
      (node (ref "J5") (pin "82") (pinfunction "82_82") (pintype "passive+no_connect"))
    )
    (net (code "252") (name "unconnected-(J5-Pad83)") (class "Default")
      (node (ref "J5") (pin "83") (pinfunction "83_83") (pintype "passive+no_connect"))
    )
    (net (code "253") (name "unconnected-(J5-Pad84)") (class "Default")
      (node (ref "J5") (pin "84") (pinfunction "84_84") (pintype "passive+no_connect"))
    )
    (net (code "254") (name "unconnected-(J5-Pad85)") (class "Default")
      (node (ref "J5") (pin "85") (pinfunction "85_85") (pintype "passive+no_connect"))
    )
    (net (code "255") (name "unconnected-(J5-Pad86)") (class "Default")
      (node (ref "J5") (pin "86") (pinfunction "86_86") (pintype "passive+no_connect"))
    )
    (net (code "256") (name "unconnected-(J5-Pad87)") (class "Default")
      (node (ref "J5") (pin "87") (pinfunction "87_87") (pintype "passive+no_connect"))
    )
    (net (code "257") (name "unconnected-(J5-Pad88)") (class "Default")
      (node (ref "J5") (pin "88") (pinfunction "88_88") (pintype "passive+no_connect"))
    )
    (net (code "258") (name "unconnected-(J5-Pad89)") (class "Default")
      (node (ref "J5") (pin "89") (pinfunction "89_89") (pintype "passive+no_connect"))
    )
    (net (code "259") (name "unconnected-(J5-Pad90)") (class "Default")
      (node (ref "J5") (pin "90") (pinfunction "90_90") (pintype "passive+no_connect"))
    )
    (net (code "260") (name "unconnected-(J5-Pad91)") (class "Default")
      (node (ref "J5") (pin "91") (pinfunction "91_91") (pintype "passive+no_connect"))
    )
    (net (code "261") (name "unconnected-(J5-Pad92)") (class "Default")
      (node (ref "J5") (pin "92") (pinfunction "92_92") (pintype "passive+no_connect"))
    )
    (net (code "262") (name "unconnected-(J5-Pad93)") (class "Default")
      (node (ref "J5") (pin "93") (pinfunction "93_93") (pintype "passive+no_connect"))
    )
    (net (code "263") (name "unconnected-(J5-Pad94)") (class "Default")
      (node (ref "J5") (pin "94") (pinfunction "94_94") (pintype "passive+no_connect"))
    )
    (net (code "264") (name "unconnected-(J5-Pad95)") (class "Default")
      (node (ref "J5") (pin "95") (pinfunction "95_95") (pintype "passive+no_connect"))
    )
    (net (code "265") (name "unconnected-(J5-Pad96)") (class "Default")
      (node (ref "J5") (pin "96") (pinfunction "96_96") (pintype "passive+no_connect"))
    )
    (net (code "266") (name "unconnected-(J5-Pad97)") (class "Default")
      (node (ref "J5") (pin "97") (pinfunction "97_97") (pintype "passive+no_connect"))
    )
    (net (code "267") (name "unconnected-(J5-Pad98)") (class "Default")
      (node (ref "J5") (pin "98") (pinfunction "98_98") (pintype "passive+no_connect"))
    )
    (net (code "268") (name "unconnected-(J5-Pad99)") (class "Default")
      (node (ref "J5") (pin "99") (pinfunction "99_99") (pintype "passive+no_connect"))
    )
    (net (code "269") (name "unconnected-(J5-Pad100)") (class "Default")
      (node (ref "J5") (pin "100") (pinfunction "100_100") (pintype "passive+no_connect"))
    )
    (net (code "270") (name "unconnected-(J5-Pad101)") (class "Default")
      (node (ref "J5") (pin "101") (pinfunction "101_101") (pintype "passive+no_connect"))
    )
    (net (code "271") (name "unconnected-(J5-Pad102)") (class "Default")
      (node (ref "J5") (pin "102") (pinfunction "102_102") (pintype "passive+no_connect"))
    )
    (net (code "272") (name "unconnected-(J5-Pad103)") (class "Default")
      (node (ref "J5") (pin "103") (pinfunction "103_103") (pintype "passive+no_connect"))
    )
    (net (code "273") (name "unconnected-(J5-Pad104)") (class "Default")
      (node (ref "J5") (pin "104") (pinfunction "104_104") (pintype "passive+no_connect"))
    )
    (net (code "274") (name "unconnected-(J5-Pad105)") (class "Default")
      (node (ref "J5") (pin "105") (pinfunction "105_105") (pintype "passive+no_connect"))
    )
    (net (code "275") (name "unconnected-(J5-Pad106)") (class "Default")
      (node (ref "J5") (pin "106") (pinfunction "106_106") (pintype "passive+no_connect"))
    )
    (net (code "276") (name "unconnected-(J5-Pad107)") (class "Default")
      (node (ref "J5") (pin "107") (pinfunction "107_107") (pintype "passive+no_connect"))
    )
    (net (code "277") (name "unconnected-(J5-Pad108)") (class "Default")
      (node (ref "J5") (pin "108") (pinfunction "108_108") (pintype "passive+no_connect"))
    )
    (net (code "278") (name "unconnected-(J5-Pad109)") (class "Default")
      (node (ref "J5") (pin "109") (pinfunction "109_109") (pintype "passive+no_connect"))
    )
    (net (code "279") (name "unconnected-(J5-Pad110)") (class "Default")
      (node (ref "J5") (pin "110") (pinfunction "110_110") (pintype "passive+no_connect"))
    )
    (net (code "280") (name "unconnected-(J5-Pad111)") (class "Default")
      (node (ref "J5") (pin "111") (pinfunction "111_111") (pintype "passive+no_connect"))
    )
    (net (code "281") (name "unconnected-(J5-Pad112)") (class "Default")
      (node (ref "J5") (pin "112") (pinfunction "112_112") (pintype "passive+no_connect"))
    )
    (net (code "282") (name "unconnected-(J5-Pad113)") (class "Default")
      (node (ref "J5") (pin "113") (pinfunction "113_113") (pintype "passive+no_connect"))
    )
    (net (code "283") (name "unconnected-(J5-Pad114)") (class "Default")
      (node (ref "J5") (pin "114") (pinfunction "114_114") (pintype "passive+no_connect"))
    )
    (net (code "284") (name "unconnected-(J5-Pad115)") (class "Default")
      (node (ref "J5") (pin "115") (pinfunction "115_115") (pintype "passive+no_connect"))
    )
    (net (code "285") (name "unconnected-(J5-Pad116)") (class "Default")
      (node (ref "J5") (pin "116") (pinfunction "116_116") (pintype "passive+no_connect"))
    )
    (net (code "286") (name "unconnected-(J5-Pad117)") (class "Default")
      (node (ref "J5") (pin "117") (pinfunction "117_117") (pintype "passive+no_connect"))
    )
    (net (code "287") (name "unconnected-(J5-Pad118)") (class "Default")
      (node (ref "J5") (pin "118") (pinfunction "118_118") (pintype "passive+no_connect"))
    )
    (net (code "288") (name "unconnected-(J5-Pad119)") (class "Default")
      (node (ref "J5") (pin "119") (pinfunction "119_119") (pintype "passive+no_connect"))
    )
    (net (code "289") (name "unconnected-(J5-Pad120)") (class "Default")
      (node (ref "J5") (pin "120") (pinfunction "120_120") (pintype "passive+no_connect"))
    )
    (net (code "290") (name "unconnected-(J5-Pad121)") (class "Default")
      (node (ref "J5") (pin "121") (pinfunction "121_121") (pintype "passive+no_connect"))
    )
    (net (code "291") (name "unconnected-(J5-Pad122)") (class "Default")
      (node (ref "J5") (pin "122") (pinfunction "122_122") (pintype "passive+no_connect"))
    )
    (net (code "292") (name "unconnected-(J5-Pad123)") (class "Default")
      (node (ref "J5") (pin "123") (pinfunction "123_123") (pintype "passive+no_connect"))
    )
    (net (code "293") (name "unconnected-(J5-Pad124)") (class "Default")
      (node (ref "J5") (pin "124") (pinfunction "124_124") (pintype "passive+no_connect"))
    )
    (net (code "294") (name "unconnected-(J5-Pad125)") (class "Default")
      (node (ref "J5") (pin "125") (pinfunction "125_125") (pintype "passive+no_connect"))
    )
    (net (code "295") (name "unconnected-(J5-Pad126)") (class "Default")
      (node (ref "J5") (pin "126") (pinfunction "126_126") (pintype "passive+no_connect"))
    )
    (net (code "296") (name "unconnected-(J5-Pad127)") (class "Default")
      (node (ref "J5") (pin "127") (pinfunction "127_127") (pintype "passive+no_connect"))
    )
    (net (code "297") (name "unconnected-(J5-Pad128)") (class "Default")
      (node (ref "J5") (pin "128") (pinfunction "128_128") (pintype "passive+no_connect"))
    )
    (net (code "298") (name "unconnected-(J5-Pad129)") (class "Default")
      (node (ref "J5") (pin "129") (pinfunction "129_129") (pintype "passive+no_connect"))
    )
    (net (code "299") (name "unconnected-(J5-Pad130)") (class "Default")
      (node (ref "J5") (pin "130") (pinfunction "130_130") (pintype "passive+no_connect"))
    )
    (net (code "300") (name "unconnected-(J5-Pad131)") (class "Default")
      (node (ref "J5") (pin "131") (pinfunction "131_131") (pintype "passive+no_connect"))
    )
    (net (code "301") (name "unconnected-(J5-Pad132)") (class "Default")
      (node (ref "J5") (pin "132") (pinfunction "132_132") (pintype "passive+no_connect"))
    )
    (net (code "302") (name "unconnected-(J5-Pad133)") (class "Default")
      (node (ref "J5") (pin "133") (pinfunction "133_133") (pintype "passive+no_connect"))
    )
    (net (code "303") (name "unconnected-(J5-Pad134)") (class "Default")
      (node (ref "J5") (pin "134") (pinfunction "134_134") (pintype "passive+no_connect"))
    )
    (net (code "304") (name "unconnected-(J5-Pad135)") (class "Default")
      (node (ref "J5") (pin "135") (pinfunction "135_135") (pintype "passive+no_connect"))
    )
    (net (code "305") (name "unconnected-(J5-Pad136)") (class "Default")
      (node (ref "J5") (pin "136") (pinfunction "136_136") (pintype "passive+no_connect"))
    )
    (net (code "306") (name "unconnected-(J5-Pad137)") (class "Default")
      (node (ref "J5") (pin "137") (pinfunction "137_137") (pintype "passive+no_connect"))
    )
    (net (code "307") (name "unconnected-(J5-Pad138)") (class "Default")
      (node (ref "J5") (pin "138") (pinfunction "138_138") (pintype "passive+no_connect"))
    )
    (net (code "308") (name "unconnected-(J5-Pad139)") (class "Default")
      (node (ref "J5") (pin "139") (pinfunction "139_139") (pintype "passive+no_connect"))
    )
    (net (code "309") (name "unconnected-(J5-Pad140)") (class "Default")
      (node (ref "J5") (pin "140") (pinfunction "140_140") (pintype "passive+no_connect"))
    )
    (net (code "310") (name "unconnected-(J5-Pad141)") (class "Default")
      (node (ref "J5") (pin "141") (pinfunction "141_141") (pintype "passive+no_connect"))
    )
    (net (code "311") (name "unconnected-(J5-Pad142)") (class "Default")
      (node (ref "J5") (pin "142") (pinfunction "142_142") (pintype "passive+no_connect"))
    )
    (net (code "312") (name "unconnected-(J5-Pad143)") (class "Default")
      (node (ref "J5") (pin "143") (pinfunction "143_143") (pintype "passive+no_connect"))
    )
    (net (code "313") (name "unconnected-(J5-Pad144)") (class "Default")
      (node (ref "J5") (pin "144") (pinfunction "144_144") (pintype "passive+no_connect"))
    )
    (net (code "314") (name "unconnected-(J5-Pad145)") (class "Default")
      (node (ref "J5") (pin "145") (pinfunction "145_145") (pintype "passive+no_connect"))
    )
    (net (code "315") (name "unconnected-(J5-Pad146)") (class "Default")
      (node (ref "J5") (pin "146") (pinfunction "146_146") (pintype "passive+no_connect"))
    )
    (net (code "316") (name "unconnected-(J5-Pad147)") (class "Default")
      (node (ref "J5") (pin "147") (pinfunction "147_147") (pintype "passive+no_connect"))
    )
    (net (code "317") (name "unconnected-(J5-Pad148)") (class "Default")
      (node (ref "J5") (pin "148") (pinfunction "148_148") (pintype "passive+no_connect"))
    )
    (net (code "318") (name "unconnected-(J5-Pad149)") (class "Default")
      (node (ref "J5") (pin "149") (pinfunction "149_149") (pintype "passive+no_connect"))
    )
    (net (code "319") (name "unconnected-(J5-Pad150)") (class "Default")
      (node (ref "J5") (pin "150") (pinfunction "150_150") (pintype "passive+no_connect"))
    )
    (net (code "320") (name "unconnected-(J5-Pad151)") (class "Default")
      (node (ref "J5") (pin "151") (pinfunction "151_151") (pintype "passive+no_connect"))
    )
    (net (code "321") (name "unconnected-(J5-Pad152)") (class "Default")
      (node (ref "J5") (pin "152") (pinfunction "152_152") (pintype "passive+no_connect"))
    )
    (net (code "322") (name "unconnected-(J5-Pad153)") (class "Default")
      (node (ref "J5") (pin "153") (pinfunction "153_153") (pintype "passive+no_connect"))
    )
    (net (code "323") (name "unconnected-(J5-Pad154)") (class "Default")
      (node (ref "J5") (pin "154") (pinfunction "154_154") (pintype "passive+no_connect"))
    )
    (net (code "324") (name "unconnected-(J5-Pad155)") (class "Default")
      (node (ref "J5") (pin "155") (pinfunction "155_155") (pintype "passive+no_connect"))
    )
    (net (code "325") (name "unconnected-(J5-Pad156)") (class "Default")
      (node (ref "J5") (pin "156") (pinfunction "156_156") (pintype "passive+no_connect"))
    )
    (net (code "326") (name "unconnected-(J5-Pad157)") (class "Default")
      (node (ref "J5") (pin "157") (pinfunction "157_157") (pintype "passive+no_connect"))
    )
    (net (code "327") (name "unconnected-(J5-Pad158)") (class "Default")
      (node (ref "J5") (pin "158") (pinfunction "158_158") (pintype "passive+no_connect"))
    )
    (net (code "328") (name "unconnected-(J5-Pad159)") (class "Default")
      (node (ref "J5") (pin "159") (pinfunction "159_159") (pintype "passive+no_connect"))
    )
    (net (code "329") (name "unconnected-(J5-Pad160)") (class "Default")
      (node (ref "J5") (pin "160") (pinfunction "160_160") (pintype "passive+no_connect"))
    )
    (net (code "330") (name "unconnected-(J5-Pad161)") (class "Default")
      (node (ref "J5") (pin "161") (pinfunction "161_161") (pintype "passive+no_connect"))
    )
    (net (code "331") (name "unconnected-(J5-Pad162)") (class "Default")
      (node (ref "J5") (pin "162") (pinfunction "162_162") (pintype "passive+no_connect"))
    )
    (net (code "332") (name "unconnected-(J5-Pad163)") (class "Default")
      (node (ref "J5") (pin "163") (pinfunction "163_163") (pintype "passive+no_connect"))
    )
    (net (code "333") (name "unconnected-(J5-Pad164)") (class "Default")
      (node (ref "J5") (pin "164") (pinfunction "164_164") (pintype "passive+no_connect"))
    )
    (net (code "334") (name "unconnected-(J5-Pad165)") (class "Default")
      (node (ref "J5") (pin "165") (pinfunction "165_165") (pintype "passive+no_connect"))
    )
    (net (code "335") (name "unconnected-(J5-Pad166)") (class "Default")
      (node (ref "J5") (pin "166") (pinfunction "166_166") (pintype "passive+no_connect"))
    )
    (net (code "336") (name "unconnected-(J5-Pad167)") (class "Default")
      (node (ref "J5") (pin "167") (pinfunction "167_167") (pintype "passive+no_connect"))
    )
    (net (code "337") (name "unconnected-(J5-Pad168)") (class "Default")
      (node (ref "J5") (pin "168") (pinfunction "168_168") (pintype "passive+no_connect"))
    )
    (net (code "338") (name "unconnected-(J5-Pad169)") (class "Default")
      (node (ref "J5") (pin "169") (pinfunction "169_169") (pintype "passive+no_connect"))
    )
    (net (code "339") (name "unconnected-(J5-Pad170)") (class "Default")
      (node (ref "J5") (pin "170") (pinfunction "170_170") (pintype "passive+no_connect"))
    )
    (net (code "340") (name "unconnected-(J5-Pad171)") (class "Default")
      (node (ref "J5") (pin "171") (pinfunction "171_171") (pintype "passive+no_connect"))
    )
    (net (code "341") (name "unconnected-(J5-Pad172)") (class "Default")
      (node (ref "J5") (pin "172") (pinfunction "172_172") (pintype "passive+no_connect"))
    )
    (net (code "342") (name "unconnected-(J5-Pad173)") (class "Default")
      (node (ref "J5") (pin "173") (pinfunction "173_173") (pintype "passive+no_connect"))
    )
    (net (code "343") (name "unconnected-(J5-Pad174)") (class "Default")
      (node (ref "J5") (pin "174") (pinfunction "174_174") (pintype "passive+no_connect"))
    )
    (net (code "344") (name "unconnected-(J5-Pad175)") (class "Default")
      (node (ref "J5") (pin "175") (pinfunction "175_175") (pintype "passive+no_connect"))
    )
    (net (code "345") (name "unconnected-(J5-Pad176)") (class "Default")
      (node (ref "J5") (pin "176") (pinfunction "176_176") (pintype "passive+no_connect"))
    )
    (net (code "346") (name "unconnected-(J5-Pad177)") (class "Default")
      (node (ref "J5") (pin "177") (pinfunction "177_177") (pintype "passive+no_connect"))
    )
    (net (code "347") (name "unconnected-(J5-Pad178)") (class "Default")
      (node (ref "J5") (pin "178") (pinfunction "178_178") (pintype "passive+no_connect"))
    )
    (net (code "348") (name "unconnected-(J5-Pad179)") (class "Default")
      (node (ref "J5") (pin "179") (pinfunction "179_179") (pintype "passive+no_connect"))
    )
    (net (code "349") (name "unconnected-(J5-Pad180)") (class "Default")
      (node (ref "J5") (pin "180") (pinfunction "180_180") (pintype "passive+no_connect"))
    )
    (net (code "350") (name "unconnected-(J5-Pad181)") (class "Default")
      (node (ref "J5") (pin "181") (pinfunction "181_181") (pintype "passive+no_connect"))
    )
    (net (code "351") (name "unconnected-(J5-Pad182)") (class "Default")
      (node (ref "J5") (pin "182") (pinfunction "182_182") (pintype "passive+no_connect"))
    )
    (net (code "352") (name "unconnected-(J5-Pad183)") (class "Default")
      (node (ref "J5") (pin "183") (pinfunction "183_183") (pintype "passive+no_connect"))
    )
    (net (code "353") (name "unconnected-(J5-Pad184)") (class "Default")
      (node (ref "J5") (pin "184") (pinfunction "184_184") (pintype "passive+no_connect"))
    )
    (net (code "354") (name "unconnected-(J5-Pad185)") (class "Default")
      (node (ref "J5") (pin "185") (pinfunction "185_185") (pintype "passive+no_connect"))
    )
    (net (code "355") (name "unconnected-(J5-Pad186)") (class "Default")
      (node (ref "J5") (pin "186") (pinfunction "186_186") (pintype "passive+no_connect"))
    )
    (net (code "356") (name "unconnected-(J5-Pad187)") (class "Default")
      (node (ref "J5") (pin "187") (pinfunction "187_187") (pintype "passive+no_connect"))
    )
    (net (code "357") (name "unconnected-(J5-Pad188)") (class "Default")
      (node (ref "J5") (pin "188") (pinfunction "188_188") (pintype "passive+no_connect"))
    )
    (net (code "358") (name "unconnected-(J5-Pad189)") (class "Default")
      (node (ref "J5") (pin "189") (pinfunction "189_189") (pintype "passive+no_connect"))
    )
    (net (code "359") (name "unconnected-(J5-Pad190)") (class "Default")
      (node (ref "J5") (pin "190") (pinfunction "190_190") (pintype "passive+no_connect"))
    )
    (net (code "360") (name "unconnected-(J5-Pad191)") (class "Default")
      (node (ref "J5") (pin "191") (pinfunction "191_191") (pintype "passive+no_connect"))
    )
    (net (code "361") (name "unconnected-(J5-Pad192)") (class "Default")
      (node (ref "J5") (pin "192") (pinfunction "192_192") (pintype "passive+no_connect"))
    )
    (net (code "362") (name "unconnected-(J5-Pad193)") (class "Default")
      (node (ref "J5") (pin "193") (pinfunction "193_193") (pintype "passive+no_connect"))
    )
    (net (code "363") (name "unconnected-(J5-Pad194)") (class "Default")
      (node (ref "J5") (pin "194") (pinfunction "194_194") (pintype "passive+no_connect"))
    )
    (net (code "364") (name "unconnected-(J5-Pad195)") (class "Default")
      (node (ref "J5") (pin "195") (pinfunction "195_195") (pintype "passive+no_connect"))
    )
    (net (code "365") (name "unconnected-(J5-Pad196)") (class "Default")
      (node (ref "J5") (pin "196") (pinfunction "196_196") (pintype "passive+no_connect"))
    )
    (net (code "366") (name "unconnected-(J5-Pad197)") (class "Default")
      (node (ref "J5") (pin "197") (pinfunction "197_197") (pintype "passive+no_connect"))
    )
    (net (code "367") (name "unconnected-(J5-Pad198)") (class "Default")
      (node (ref "J5") (pin "198") (pinfunction "198_198") (pintype "passive+no_connect"))
    )
    (net (code "368") (name "unconnected-(J5-Pad199)") (class "Default")
      (node (ref "J5") (pin "199") (pinfunction "199_199") (pintype "passive+no_connect"))
    )
    (net (code "369") (name "unconnected-(J5-Pad200)") (class "Default")
      (node (ref "J5") (pin "200") (pinfunction "200_200") (pintype "passive+no_connect"))
    )
    (net (code "370") (name "unconnected-(J7-Pad5)") (class "Default")
      (node (ref "J7") (pin "5") (pinfunction "5_5") (pintype "passive+no_connect"))
    )
    (net (code "371") (name "unconnected-(J7-Pad6)") (class "Default")
      (node (ref "J7") (pin "6") (pinfunction "6_6") (pintype "passive+no_connect"))
    )
    (net (code "372") (name "unconnected-(J7-Pad19)") (class "Default")
      (node (ref "J7") (pin "19") (pinfunction "19_19") (pintype "passive+no_connect"))
    )
    (net (code "373") (name "unconnected-(J7-Pad20)") (class "Default")
      (node (ref "J7") (pin "20") (pinfunction "20_20") (pintype "passive+no_connect"))
    )
    (net (code "374") (name "unconnected-(J7-Pad37)") (class "Default")
      (node (ref "J7") (pin "37") (pinfunction "37_37") (pintype "passive+no_connect"))
    )
    (net (code "375") (name "unconnected-(J7-Pad38)") (class "Default")
      (node (ref "J7") (pin "38") (pinfunction "38_38") (pintype "passive+no_connect"))
    )
    (net (code "376") (name "unconnected-(J7-Pad42)") (class "Default")
      (node (ref "J7") (pin "42") (pinfunction "42_42") (pintype "passive+no_connect"))
    )
    (net (code "377") (name "unconnected-(J7-Pad56)") (class "Default")
      (node (ref "J7") (pin "56") (pinfunction "56_56") (pintype "passive+no_connect"))
    )
    (net (code "378") (name "unconnected-(J7-Pad57)") (class "Default")
      (node (ref "J7") (pin "57") (pinfunction "57_57") (pintype "passive+no_connect"))
    )
    (net (code "379") (name "unconnected-(J7-Pad58)") (class "Default")
      (node (ref "J7") (pin "58") (pinfunction "58_58") (pintype "passive+no_connect"))
    )
    (net (code "380") (name "unconnected-(J7-Pad77)") (class "Default")
      (node (ref "J7") (pin "77") (pinfunction "77_77") (pintype "passive+no_connect"))
    )
    (net (code "381") (name "unconnected-(J7-Pad78)") (class "Default")
      (node (ref "J7") (pin "78") (pinfunction "78_78") (pintype "passive+no_connect"))
    )
    (net (code "382") (name "unconnected-(J7-Pad81)") (class "Default")
      (node (ref "J7") (pin "81") (pinfunction "81_81") (pintype "passive+no_connect"))
    )
    (net (code "383") (name "unconnected-(J7-Pad82)") (class "Default")
      (node (ref "J7") (pin "82") (pinfunction "82_82") (pintype "passive+no_connect"))
    )
    (net (code "384") (name "unconnected-(J7-Pad83)") (class "Default")
      (node (ref "J7") (pin "83") (pinfunction "83_83") (pintype "passive+no_connect"))
    )
    (net (code "385") (name "unconnected-(J7-Pad84)") (class "Default")
      (node (ref "J7") (pin "84") (pinfunction "84_84") (pintype "passive+no_connect"))
    )
    (net (code "386") (name "unconnected-(J7-Pad85)") (class "Default")
      (node (ref "J7") (pin "85") (pinfunction "85_85") (pintype "passive+no_connect"))
    )
    (net (code "387") (name "unconnected-(J7-Pad86)") (class "Default")
      (node (ref "J7") (pin "86") (pinfunction "86_86") (pintype "passive+no_connect"))
    )
    (net (code "388") (name "unconnected-(J7-Pad87)") (class "Default")
      (node (ref "J7") (pin "87") (pinfunction "87_87") (pintype "passive+no_connect"))
    )
    (net (code "389") (name "unconnected-(J7-Pad88)") (class "Default")
      (node (ref "J7") (pin "88") (pinfunction "88_88") (pintype "passive+no_connect"))
    )
    (net (code "390") (name "unconnected-(J7-Pad89)") (class "Default")
      (node (ref "J7") (pin "89") (pinfunction "89_89") (pintype "passive+no_connect"))
    )
    (net (code "391") (name "unconnected-(J7-Pad90)") (class "Default")
      (node (ref "J7") (pin "90") (pinfunction "90_90") (pintype "passive+no_connect"))
    )
    (net (code "392") (name "unconnected-(J7-Pad91)") (class "Default")
      (node (ref "J7") (pin "91") (pinfunction "91_91") (pintype "passive+no_connect"))
    )
    (net (code "393") (name "unconnected-(J7-Pad92)") (class "Default")
      (node (ref "J7") (pin "92") (pinfunction "92_92") (pintype "passive+no_connect"))
    )
    (net (code "394") (name "unconnected-(J7-Pad93)") (class "Default")
      (node (ref "J7") (pin "93") (pinfunction "93_93") (pintype "passive+no_connect"))
    )
    (net (code "395") (name "unconnected-(J7-Pad94)") (class "Default")
      (node (ref "J7") (pin "94") (pinfunction "94_94") (pintype "passive+no_connect"))
    )
    (net (code "396") (name "unconnected-(J7-Pad95)") (class "Default")
      (node (ref "J7") (pin "95") (pinfunction "95_95") (pintype "passive+no_connect"))
    )
    (net (code "397") (name "unconnected-(J7-Pad96)") (class "Default")
      (node (ref "J7") (pin "96") (pinfunction "96_96") (pintype "passive+no_connect"))
    )
    (net (code "398") (name "unconnected-(J7-Pad97)") (class "Default")
      (node (ref "J7") (pin "97") (pinfunction "97_97") (pintype "passive+no_connect"))
    )
    (net (code "399") (name "unconnected-(J7-Pad98)") (class "Default")
      (node (ref "J7") (pin "98") (pinfunction "98_98") (pintype "passive+no_connect"))
    )
    (net (code "400") (name "unconnected-(J7-Pad101)") (class "Default")
      (node (ref "J7") (pin "101") (pinfunction "101_101") (pintype "passive+no_connect"))
    )
    (net (code "401") (name "unconnected-(J7-Pad102)") (class "Default")
      (node (ref "J7") (pin "102") (pinfunction "102_102") (pintype "passive+no_connect"))
    )
    (net (code "402") (name "unconnected-(J7-Pad103)") (class "Default")
      (node (ref "J7") (pin "103") (pinfunction "103_103") (pintype "passive+no_connect"))
    )
    (net (code "403") (name "unconnected-(J7-Pad104)") (class "Default")
      (node (ref "J7") (pin "104") (pinfunction "104_104") (pintype "passive+no_connect"))
    )
    (net (code "404") (name "unconnected-(J7-Pad105)") (class "Default")
      (node (ref "J7") (pin "105") (pinfunction "105_105") (pintype "passive+no_connect"))
    )
    (net (code "405") (name "unconnected-(J7-Pad106)") (class "Default")
      (node (ref "J7") (pin "106") (pinfunction "106_106") (pintype "passive+no_connect"))
    )
    (net (code "406") (name "unconnected-(J7-Pad107)") (class "Default")
      (node (ref "J7") (pin "107") (pinfunction "107_107") (pintype "passive+no_connect"))
    )
    (net (code "407") (name "unconnected-(J7-Pad108)") (class "Default")
      (node (ref "J7") (pin "108") (pinfunction "108_108") (pintype "passive+no_connect"))
    )
    (net (code "408") (name "unconnected-(J7-Pad109)") (class "Default")
      (node (ref "J7") (pin "109") (pinfunction "109_109") (pintype "passive+no_connect"))
    )
    (net (code "409") (name "unconnected-(J7-Pad110)") (class "Default")
      (node (ref "J7") (pin "110") (pinfunction "110_110") (pintype "passive+no_connect"))
    )
    (net (code "410") (name "unconnected-(J7-Pad111)") (class "Default")
      (node (ref "J7") (pin "111") (pinfunction "111_111") (pintype "passive+no_connect"))
    )
    (net (code "411") (name "unconnected-(J7-Pad112)") (class "Default")
      (node (ref "J7") (pin "112") (pinfunction "112_112") (pintype "passive+no_connect"))
    )
    (net (code "412") (name "unconnected-(J7-Pad113)") (class "Default")
      (node (ref "J7") (pin "113") (pinfunction "113_113") (pintype "passive+no_connect"))
    )
    (net (code "413") (name "unconnected-(J7-Pad114)") (class "Default")
      (node (ref "J7") (pin "114") (pinfunction "114_114") (pintype "passive+no_connect"))
    )
    (net (code "414") (name "unconnected-(J7-Pad115)") (class "Default")
      (node (ref "J7") (pin "115") (pinfunction "115_115") (pintype "passive+no_connect"))
    )
    (net (code "415") (name "unconnected-(J7-Pad116)") (class "Default")
      (node (ref "J7") (pin "116") (pinfunction "116_116") (pintype "passive+no_connect"))
    )
    (net (code "416") (name "unconnected-(J7-Pad117)") (class "Default")
      (node (ref "J7") (pin "117") (pinfunction "117_117") (pintype "passive+no_connect"))
    )
    (net (code "417") (name "unconnected-(J7-Pad118)") (class "Default")
      (node (ref "J7") (pin "118") (pinfunction "118_118") (pintype "passive+no_connect"))
    )
    (net (code "418") (name "unconnected-(J7-Pad121)") (class "Default")
      (node (ref "J7") (pin "121") (pinfunction "121_121") (pintype "passive+no_connect"))
    )
    (net (code "419") (name "unconnected-(J7-Pad122)") (class "Default")
      (node (ref "J7") (pin "122") (pinfunction "122_122") (pintype "passive+no_connect"))
    )
    (net (code "420") (name "unconnected-(J7-Pad123)") (class "Default")
      (node (ref "J7") (pin "123") (pinfunction "123_123") (pintype "passive+no_connect"))
    )
    (net (code "421") (name "unconnected-(J7-Pad124)") (class "Default")
      (node (ref "J7") (pin "124") (pinfunction "124_124") (pintype "passive+no_connect"))
    )
    (net (code "422") (name "unconnected-(J7-Pad125)") (class "Default")
      (node (ref "J7") (pin "125") (pinfunction "125_125") (pintype "passive+no_connect"))
    )
    (net (code "423") (name "unconnected-(J7-Pad126)") (class "Default")
      (node (ref "J7") (pin "126") (pinfunction "126_126") (pintype "passive+no_connect"))
    )
    (net (code "424") (name "unconnected-(J7-Pad127)") (class "Default")
      (node (ref "J7") (pin "127") (pinfunction "127_127") (pintype "passive+no_connect"))
    )
    (net (code "425") (name "unconnected-(J7-Pad128)") (class "Default")
      (node (ref "J7") (pin "128") (pinfunction "128_128") (pintype "passive+no_connect"))
    )
    (net (code "426") (name "unconnected-(J7-Pad129)") (class "Default")
      (node (ref "J7") (pin "129") (pinfunction "129_129") (pintype "passive+no_connect"))
    )
    (net (code "427") (name "unconnected-(J7-Pad130)") (class "Default")
      (node (ref "J7") (pin "130") (pinfunction "130_130") (pintype "passive+no_connect"))
    )
    (net (code "428") (name "unconnected-(J7-Pad131)") (class "Default")
      (node (ref "J7") (pin "131") (pinfunction "131_131") (pintype "passive+no_connect"))
    )
    (net (code "429") (name "unconnected-(J7-Pad132)") (class "Default")
      (node (ref "J7") (pin "132") (pinfunction "132_132") (pintype "passive+no_connect"))
    )
    (net (code "430") (name "unconnected-(J7-Pad133)") (class "Default")
      (node (ref "J7") (pin "133") (pinfunction "133_133") (pintype "passive+no_connect"))
    )
    (net (code "431") (name "unconnected-(J7-Pad134)") (class "Default")
      (node (ref "J7") (pin "134") (pinfunction "134_134") (pintype "passive+no_connect"))
    )
    (net (code "432") (name "unconnected-(J7-Pad135)") (class "Default")
      (node (ref "J7") (pin "135") (pinfunction "135_135") (pintype "passive+no_connect"))
    )
    (net (code "433") (name "unconnected-(J7-Pad136)") (class "Default")
      (node (ref "J7") (pin "136") (pinfunction "136_136") (pintype "passive+no_connect"))
    )
    (net (code "434") (name "unconnected-(J7-Pad137)") (class "Default")
      (node (ref "J7") (pin "137") (pinfunction "137_137") (pintype "passive+no_connect"))
    )
    (net (code "435") (name "unconnected-(J7-Pad138)") (class "Default")
      (node (ref "J7") (pin "138") (pinfunction "138_138") (pintype "passive+no_connect"))
    )
    (net (code "436") (name "unconnected-(J7-Pad141)") (class "Default")
      (node (ref "J7") (pin "141") (pinfunction "141_141") (pintype "passive+no_connect"))
    )
    (net (code "437") (name "unconnected-(J7-Pad142)") (class "Default")
      (node (ref "J7") (pin "142") (pinfunction "142_142") (pintype "passive+no_connect"))
    )
    (net (code "438") (name "unconnected-(J7-Pad143)") (class "Default")
      (node (ref "J7") (pin "143") (pinfunction "143_143") (pintype "passive+no_connect"))
    )
    (net (code "439") (name "unconnected-(J7-Pad144)") (class "Default")
      (node (ref "J7") (pin "144") (pinfunction "144_144") (pintype "passive+no_connect"))
    )
    (net (code "440") (name "unconnected-(J7-Pad145)") (class "Default")
      (node (ref "J7") (pin "145") (pinfunction "145_145") (pintype "passive+no_connect"))
    )
    (net (code "441") (name "unconnected-(J7-Pad146)") (class "Default")
      (node (ref "J7") (pin "146") (pinfunction "146_146") (pintype "passive+no_connect"))
    )
    (net (code "442") (name "unconnected-(J7-Pad147)") (class "Default")
      (node (ref "J7") (pin "147") (pinfunction "147_147") (pintype "passive+no_connect"))
    )
    (net (code "443") (name "unconnected-(J7-Pad148)") (class "Default")
      (node (ref "J7") (pin "148") (pinfunction "148_148") (pintype "passive+no_connect"))
    )
    (net (code "444") (name "unconnected-(J7-Pad149)") (class "Default")
      (node (ref "J7") (pin "149") (pinfunction "149_149") (pintype "passive+no_connect"))
    )
    (net (code "445") (name "unconnected-(J7-Pad150)") (class "Default")
      (node (ref "J7") (pin "150") (pinfunction "150_150") (pintype "passive+no_connect"))
    )
    (net (code "446") (name "unconnected-(J7-Pad151)") (class "Default")
      (node (ref "J7") (pin "151") (pinfunction "151_151") (pintype "passive+no_connect"))
    )
    (net (code "447") (name "unconnected-(J7-Pad152)") (class "Default")
      (node (ref "J7") (pin "152") (pinfunction "152_152") (pintype "passive+no_connect"))
    )
    (net (code "448") (name "unconnected-(J7-Pad153)") (class "Default")
      (node (ref "J7") (pin "153") (pinfunction "153_153") (pintype "passive+no_connect"))
    )
    (net (code "449") (name "unconnected-(J7-Pad154)") (class "Default")
      (node (ref "J7") (pin "154") (pinfunction "154_154") (pintype "passive+no_connect"))
    )
    (net (code "450") (name "unconnected-(J7-Pad155)") (class "Default")
      (node (ref "J7") (pin "155") (pinfunction "155_155") (pintype "passive+no_connect"))
    )
    (net (code "451") (name "unconnected-(J7-Pad156)") (class "Default")
      (node (ref "J7") (pin "156") (pinfunction "156_156") (pintype "passive+no_connect"))
    )
    (net (code "452") (name "unconnected-(J7-Pad157)") (class "Default")
      (node (ref "J7") (pin "157") (pinfunction "157_157") (pintype "passive+no_connect"))
    )
    (net (code "453") (name "unconnected-(J7-Pad158)") (class "Default")
      (node (ref "J7") (pin "158") (pinfunction "158_158") (pintype "passive+no_connect"))
    )
    (net (code "454") (name "unconnected-(J7-Pad161)") (class "Default")
      (node (ref "J7") (pin "161") (pinfunction "161_161") (pintype "passive+no_connect"))
    )
    (net (code "455") (name "unconnected-(J7-Pad162)") (class "Default")
      (node (ref "J7") (pin "162") (pinfunction "162_162") (pintype "passive+no_connect"))
    )
    (net (code "456") (name "unconnected-(J7-Pad163)") (class "Default")
      (node (ref "J7") (pin "163") (pinfunction "163_163") (pintype "passive+no_connect"))
    )
    (net (code "457") (name "unconnected-(J7-Pad164)") (class "Default")
      (node (ref "J7") (pin "164") (pinfunction "164_164") (pintype "passive+no_connect"))
    )
    (net (code "458") (name "unconnected-(J7-Pad165)") (class "Default")
      (node (ref "J7") (pin "165") (pinfunction "165_165") (pintype "passive+no_connect"))
    )
    (net (code "459") (name "unconnected-(J7-Pad166)") (class "Default")
      (node (ref "J7") (pin "166") (pinfunction "166_166") (pintype "passive+no_connect"))
    )
    (net (code "460") (name "unconnected-(J7-Pad167)") (class "Default")
      (node (ref "J7") (pin "167") (pinfunction "167_167") (pintype "passive+no_connect"))
    )
    (net (code "461") (name "unconnected-(J7-Pad168)") (class "Default")
      (node (ref "J7") (pin "168") (pinfunction "168_168") (pintype "passive+no_connect"))
    )
    (net (code "462") (name "unconnected-(J7-Pad169)") (class "Default")
      (node (ref "J7") (pin "169") (pinfunction "169_169") (pintype "passive+no_connect"))
    )
    (net (code "463") (name "unconnected-(J7-Pad170)") (class "Default")
      (node (ref "J7") (pin "170") (pinfunction "170_170") (pintype "passive+no_connect"))
    )
    (net (code "464") (name "unconnected-(J7-Pad171)") (class "Default")
      (node (ref "J7") (pin "171") (pinfunction "171_171") (pintype "passive+no_connect"))
    )
    (net (code "465") (name "unconnected-(J7-Pad172)") (class "Default")
      (node (ref "J7") (pin "172") (pinfunction "172_172") (pintype "passive+no_connect"))
    )
    (net (code "466") (name "unconnected-(J7-Pad173)") (class "Default")
      (node (ref "J7") (pin "173") (pinfunction "173_173") (pintype "passive+no_connect"))
    )
    (net (code "467") (name "unconnected-(J7-Pad174)") (class "Default")
      (node (ref "J7") (pin "174") (pinfunction "174_174") (pintype "passive+no_connect"))
    )
    (net (code "468") (name "unconnected-(J7-Pad175)") (class "Default")
      (node (ref "J7") (pin "175") (pinfunction "175_175") (pintype "passive+no_connect"))
    )
    (net (code "469") (name "unconnected-(J7-Pad176)") (class "Default")
      (node (ref "J7") (pin "176") (pinfunction "176_176") (pintype "passive+no_connect"))
    )
    (net (code "470") (name "unconnected-(J7-Pad177)") (class "Default")
      (node (ref "J7") (pin "177") (pinfunction "177_177") (pintype "passive+no_connect"))
    )
    (net (code "471") (name "unconnected-(J7-Pad178)") (class "Default")
      (node (ref "J7") (pin "178") (pinfunction "178_178") (pintype "passive+no_connect"))
    )
    (net (code "472") (name "unconnected-(J7-Pad181)") (class "Default")
      (node (ref "J7") (pin "181") (pinfunction "181_181") (pintype "passive+no_connect"))
    )
    (net (code "473") (name "unconnected-(J7-Pad182)") (class "Default")
      (node (ref "J7") (pin "182") (pinfunction "182_182") (pintype "passive+no_connect"))
    )
    (net (code "474") (name "unconnected-(J7-Pad183)") (class "Default")
      (node (ref "J7") (pin "183") (pinfunction "183_183") (pintype "passive+no_connect"))
    )
    (net (code "475") (name "unconnected-(J7-Pad184)") (class "Default")
      (node (ref "J7") (pin "184") (pinfunction "184_184") (pintype "passive+no_connect"))
    )
    (net (code "476") (name "unconnected-(J7-Pad185)") (class "Default")
      (node (ref "J7") (pin "185") (pinfunction "185_185") (pintype "passive+no_connect"))
    )
    (net (code "477") (name "unconnected-(J7-Pad186)") (class "Default")
      (node (ref "J7") (pin "186") (pinfunction "186_186") (pintype "passive+no_connect"))
    )
    (net (code "478") (name "unconnected-(J7-Pad187)") (class "Default")
      (node (ref "J7") (pin "187") (pinfunction "187_187") (pintype "passive+no_connect"))
    )
    (net (code "479") (name "unconnected-(J7-Pad188)") (class "Default")
      (node (ref "J7") (pin "188") (pinfunction "188_188") (pintype "passive+no_connect"))
    )
    (net (code "480") (name "unconnected-(J7-Pad189)") (class "Default")
      (node (ref "J7") (pin "189") (pinfunction "189_189") (pintype "passive+no_connect"))
    )
    (net (code "481") (name "unconnected-(J7-Pad190)") (class "Default")
      (node (ref "J7") (pin "190") (pinfunction "190_190") (pintype "passive+no_connect"))
    )
    (net (code "482") (name "unconnected-(J7-Pad191)") (class "Default")
      (node (ref "J7") (pin "191") (pinfunction "191_191") (pintype "passive+no_connect"))
    )
    (net (code "483") (name "unconnected-(J7-Pad192)") (class "Default")
      (node (ref "J7") (pin "192") (pinfunction "192_192") (pintype "passive+no_connect"))
    )
    (net (code "484") (name "unconnected-(J7-Pad193)") (class "Default")
      (node (ref "J7") (pin "193") (pinfunction "193_193") (pintype "passive+no_connect"))
    )
    (net (code "485") (name "unconnected-(J7-Pad194)") (class "Default")
      (node (ref "J7") (pin "194") (pinfunction "194_194") (pintype "passive+no_connect"))
    )
    (net (code "486") (name "unconnected-(J7-Pad195)") (class "Default")
      (node (ref "J7") (pin "195") (pinfunction "195_195") (pintype "passive+no_connect"))
    )
    (net (code "487") (name "unconnected-(J7-Pad196)") (class "Default")
      (node (ref "J7") (pin "196") (pinfunction "196_196") (pintype "passive+no_connect"))
    )
    (net (code "488") (name "unconnected-(J7-Pad197)") (class "Default")
      (node (ref "J7") (pin "197") (pinfunction "197_197") (pintype "passive+no_connect"))
    )
    (net (code "489") (name "unconnected-(J7-Pad198)") (class "Default")
      (node (ref "J7") (pin "198") (pinfunction "198_198") (pintype "passive+no_connect"))
    )
  )
)
